# LED_Cube.net
KiCad netlist of a schematic drawn in EAGLE
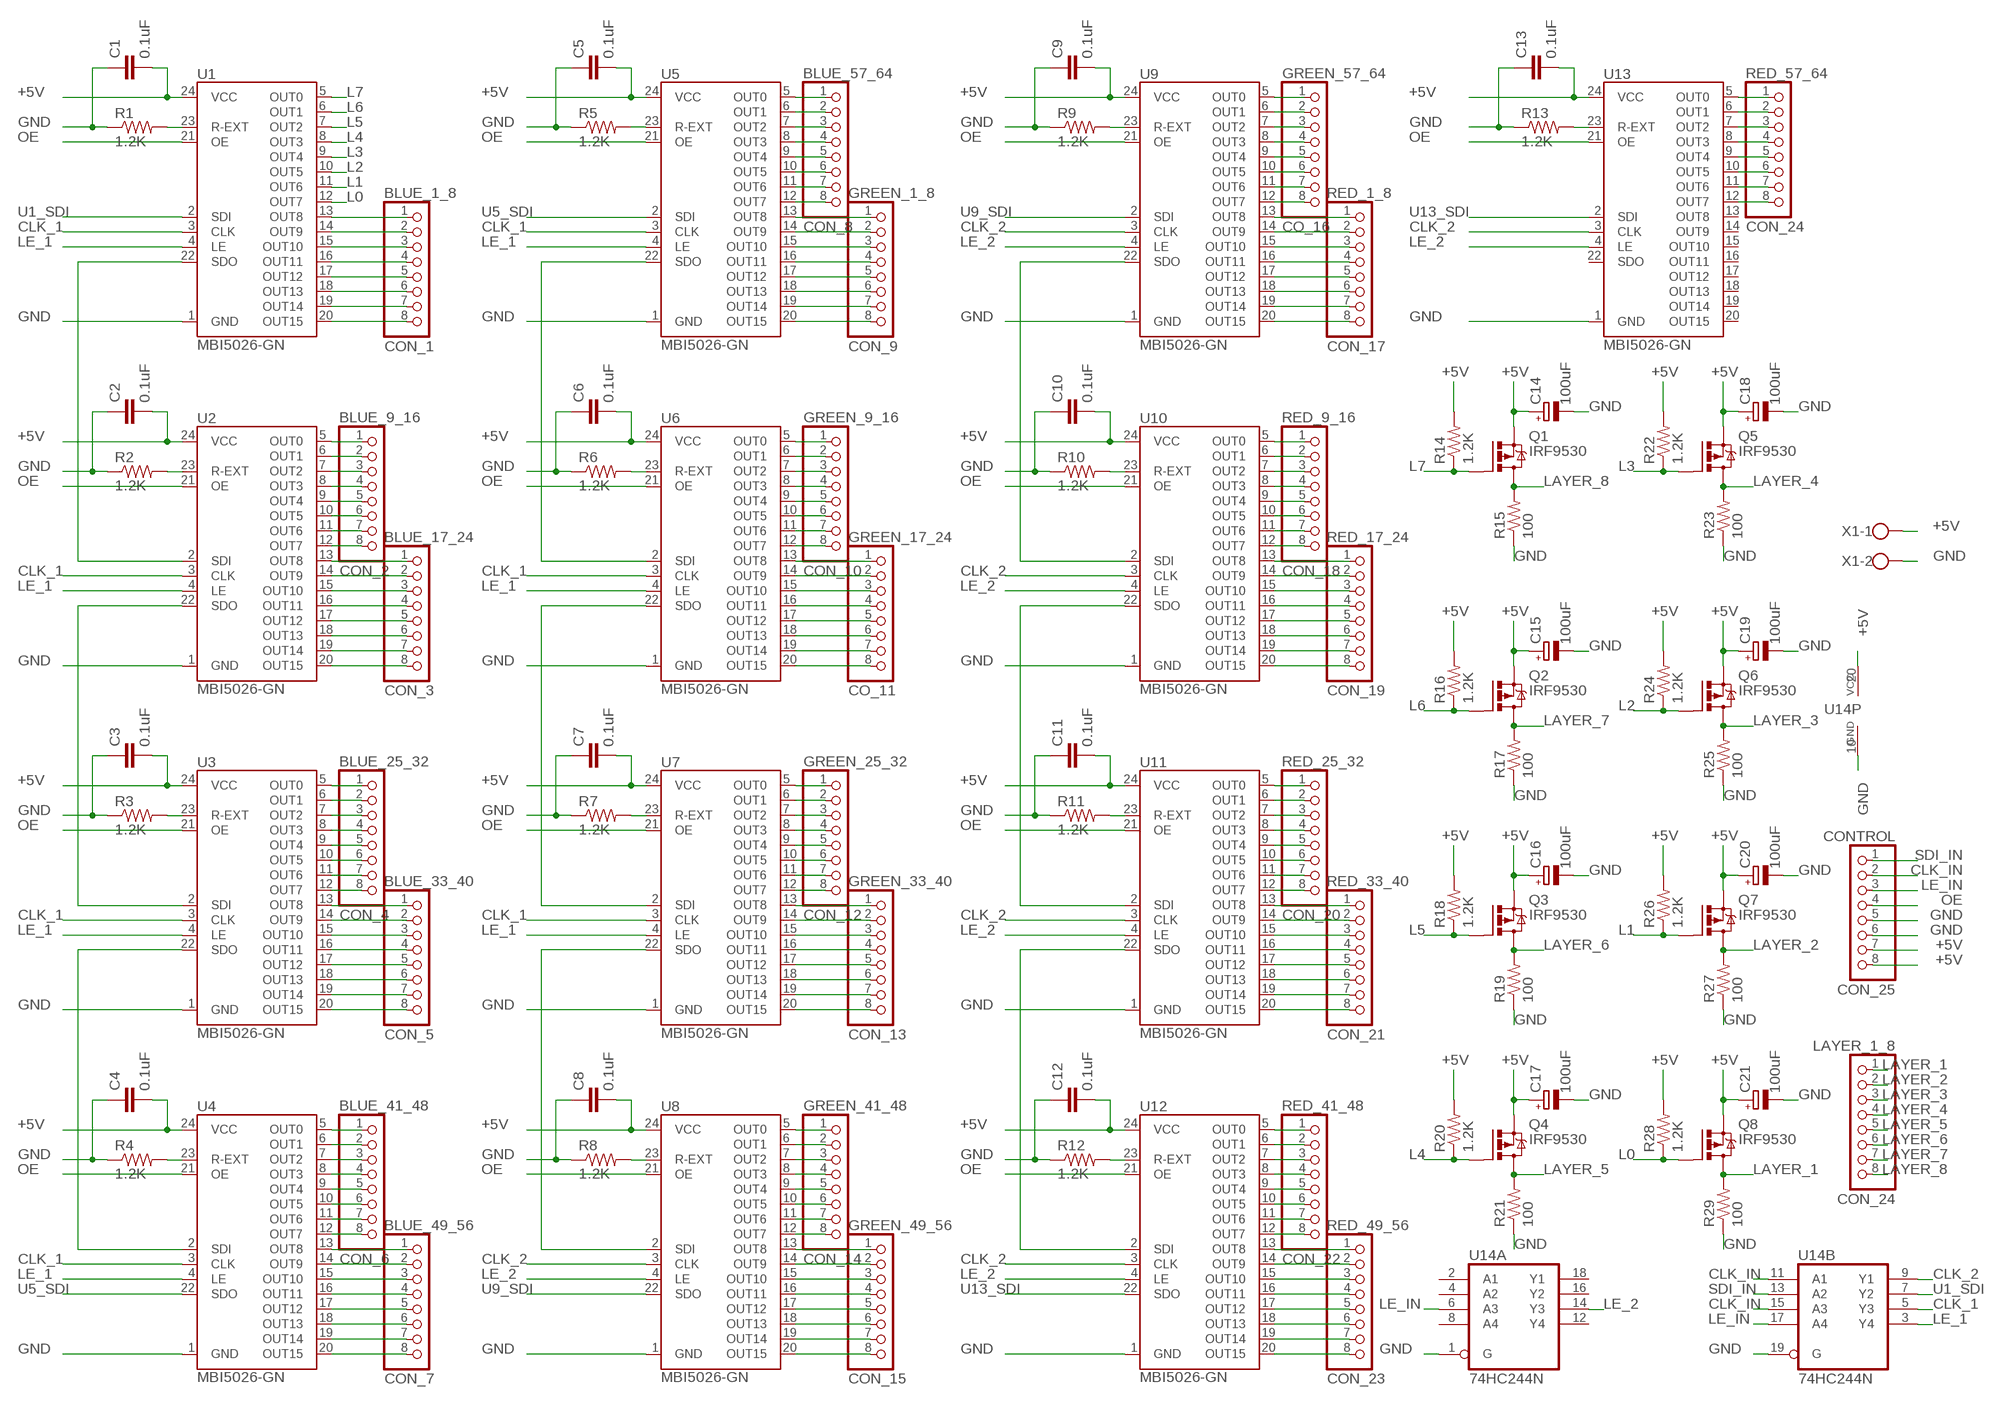
[diagram p0: schematic, sheet 1]

(export (version "E")
  (design (tool "Eeschema 10.0.6"))
  (components
    (comp (ref "BLUE_1_8")
      (value "CON_1")
      (footprint "eagle-import:1X08-BIG")
      (libsource (lib "eagle-import") (part "PINHD-1X8BIG"))
    )
    (comp (ref "BLUE_9_16")
      (value "CON_2")
      (footprint "eagle-import:1X08-BIG")
      (libsource (lib "eagle-import") (part "PINHD-1X8BIG"))
    )
    (comp (ref "BLUE_17_24")
      (value "CON_3")
      (footprint "eagle-import:1X08-BIG")
      (libsource (lib "eagle-import") (part "PINHD-1X8BIG"))
    )
    (comp (ref "BLUE_25_32")
      (value "CON_4")
      (footprint "eagle-import:1X08-BIG")
      (libsource (lib "eagle-import") (part "PINHD-1X8BIG"))
    )
    (comp (ref "BLUE_33_40")
      (value "CON_5")
      (footprint "eagle-import:1X08-BIG")
      (libsource (lib "eagle-import") (part "PINHD-1X8BIG"))
    )
    (comp (ref "BLUE_41_48")
      (value "CON_6")
      (footprint "eagle-import:1X08-BIG")
      (libsource (lib "eagle-import") (part "PINHD-1X8BIG"))
    )
    (comp (ref "BLUE_49_56")
      (value "CON_7")
      (footprint "eagle-import:1X08-BIG")
      (libsource (lib "eagle-import") (part "PINHD-1X8BIG"))
    )
    (comp (ref "BLUE_57_64")
      (value "CON_8")
      (footprint "eagle-import:1X08-BIG")
      (libsource (lib "eagle-import") (part "PINHD-1X8BIG"))
    )
    (comp (ref "C1")
      (value "0.1uF")
      (footprint "eagle-import:C2.5-3")
      (libsource (lib "eagle-import") (part "C2,5-3"))
    )
    (comp (ref "C2")
      (value "0.1uF")
      (footprint "eagle-import:C2.5-3")
      (libsource (lib "eagle-import") (part "C2,5-3"))
    )
    (comp (ref "C3")
      (value "0.1uF")
      (footprint "eagle-import:C2.5-3")
      (libsource (lib "eagle-import") (part "C2,5-3"))
    )
    (comp (ref "C4")
      (value "0.1uF")
      (footprint "eagle-import:C2.5-3")
      (libsource (lib "eagle-import") (part "C2,5-3"))
    )
    (comp (ref "C5")
      (value "0.1uF")
      (footprint "eagle-import:C2.5-3")
      (libsource (lib "eagle-import") (part "C2,5-3"))
    )
    (comp (ref "C6")
      (value "0.1uF")
      (footprint "eagle-import:C2.5-3")
      (libsource (lib "eagle-import") (part "C2,5-3"))
    )
    (comp (ref "C7")
      (value "0.1uF")
      (footprint "eagle-import:C2.5-3")
      (libsource (lib "eagle-import") (part "C2,5-3"))
    )
    (comp (ref "C8")
      (value "0.1uF")
      (footprint "eagle-import:C2.5-3")
      (libsource (lib "eagle-import") (part "C2,5-3"))
    )
    (comp (ref "C9")
      (value "0.1uF")
      (footprint "eagle-import:C2.5-3")
      (libsource (lib "eagle-import") (part "C2,5-3"))
    )
    (comp (ref "C10")
      (value "0.1uF")
      (footprint "eagle-import:C2.5-3")
      (libsource (lib "eagle-import") (part "C2,5-3"))
    )
    (comp (ref "C11")
      (value "0.1uF")
      (footprint "eagle-import:C2.5-3")
      (libsource (lib "eagle-import") (part "C2,5-3"))
    )
    (comp (ref "C12")
      (value "0.1uF")
      (footprint "eagle-import:C2.5-3")
      (libsource (lib "eagle-import") (part "C2,5-3"))
    )
    (comp (ref "C13")
      (value "0.1uF")
      (footprint "eagle-import:C2.5-3")
      (libsource (lib "eagle-import") (part "C2,5-3"))
    )
    (comp (ref "C14")
      (value "100uF")
      (footprint "eagle-import:E5-6")
      (libsource (lib "eagle-import") (part "CPOL-EUE5-6"))
    )
    (comp (ref "C15")
      (value "100uF")
      (footprint "eagle-import:E5-6")
      (libsource (lib "eagle-import") (part "CPOL-EUE5-6"))
    )
    (comp (ref "C16")
      (value "100uF")
      (footprint "eagle-import:E5-6")
      (libsource (lib "eagle-import") (part "CPOL-EUE5-6"))
    )
    (comp (ref "C17")
      (value "100uF")
      (footprint "eagle-import:E5-6")
      (libsource (lib "eagle-import") (part "CPOL-EUE5-6"))
    )
    (comp (ref "C18")
      (value "100uF")
      (footprint "eagle-import:E5-6")
      (libsource (lib "eagle-import") (part "CPOL-EUE5-6"))
    )
    (comp (ref "C19")
      (value "100uF")
      (footprint "eagle-import:E5-6")
      (libsource (lib "eagle-import") (part "CPOL-EUE5-6"))
    )
    (comp (ref "C20")
      (value "100uF")
      (footprint "eagle-import:E5-6")
      (libsource (lib "eagle-import") (part "CPOL-EUE5-6"))
    )
    (comp (ref "C21")
      (value "100uF")
      (footprint "eagle-import:E5-6")
      (libsource (lib "eagle-import") (part "CPOL-EUE5-6"))
    )
    (comp (ref "CONTROL")
      (value "CON_25")
      (footprint "eagle-import:1X08-BIG")
      (libsource (lib "eagle-import") (part "PINHD-1X8BIG"))
    )
    (comp (ref "GREEN_1_8")
      (value "CON_9")
      (footprint "eagle-import:1X08-BIG")
      (libsource (lib "eagle-import") (part "PINHD-1X8BIG"))
    )
    (comp (ref "GREEN_9_16")
      (value "CON_10")
      (footprint "eagle-import:1X08-BIG")
      (libsource (lib "eagle-import") (part "PINHD-1X8BIG"))
    )
    (comp (ref "GREEN_17_24")
      (value "CO_11")
      (footprint "eagle-import:1X08-BIG")
      (libsource (lib "eagle-import") (part "PINHD-1X8BIG"))
    )
    (comp (ref "GREEN_25_32")
      (value "CON_12")
      (footprint "eagle-import:1X08-BIG")
      (libsource (lib "eagle-import") (part "PINHD-1X8BIG"))
    )
    (comp (ref "GREEN_33_40")
      (value "CON_13")
      (footprint "eagle-import:1X08-BIG")
      (libsource (lib "eagle-import") (part "PINHD-1X8BIG"))
    )
    (comp (ref "GREEN_41_48")
      (value "CON_14")
      (footprint "eagle-import:1X08-BIG")
      (libsource (lib "eagle-import") (part "PINHD-1X8BIG"))
    )
    (comp (ref "GREEN_49_56")
      (value "CON_15")
      (footprint "eagle-import:1X08-BIG")
      (libsource (lib "eagle-import") (part "PINHD-1X8BIG"))
    )
    (comp (ref "GREEN_57_64")
      (value "CO_16")
      (footprint "eagle-import:1X08-BIG")
      (libsource (lib "eagle-import") (part "PINHD-1X8BIG"))
    )
    (comp (ref "LAYER_1_8")
      (value "CON_24")
      (footprint "eagle-import:1X08-BIG")
      (libsource (lib "eagle-import") (part "PINHD-1X8BIG"))
    )
    (comp (ref "Q1")
      (value "IRF9530")
      (footprint "eagle-import:TO220BV")
      (libsource (lib "eagle-import") (part "IRF9530"))
    )
    (comp (ref "Q2")
      (value "IRF9530")
      (footprint "eagle-import:TO220BV")
      (libsource (lib "eagle-import") (part "IRF9530"))
    )
    (comp (ref "Q3")
      (value "IRF9530")
      (footprint "eagle-import:TO220BV")
      (libsource (lib "eagle-import") (part "IRF9530"))
    )
    (comp (ref "Q4")
      (value "IRF9530")
      (footprint "eagle-import:TO220BV")
      (libsource (lib "eagle-import") (part "IRF9530"))
    )
    (comp (ref "Q5")
      (value "IRF9530")
      (footprint "eagle-import:TO220BV")
      (libsource (lib "eagle-import") (part "IRF9530"))
    )
    (comp (ref "Q6")
      (value "IRF9530")
      (footprint "eagle-import:TO220BV")
      (libsource (lib "eagle-import") (part "IRF9530"))
    )
    (comp (ref "Q7")
      (value "IRF9530")
      (footprint "eagle-import:TO220BV")
      (libsource (lib "eagle-import") (part "IRF9530"))
    )
    (comp (ref "Q8")
      (value "IRF9530")
      (footprint "eagle-import:TO220BV")
      (libsource (lib "eagle-import") (part "IRF9530"))
    )
    (comp (ref "R1")
      (value "1.2K")
      (footprint "eagle-import:0207_15")
      (libsource (lib "eagle-import") (part "R-US_0207/15"))
    )
    (comp (ref "R2")
      (value "1.2K")
      (footprint "eagle-import:0207_15")
      (libsource (lib "eagle-import") (part "R-US_0207/15"))
    )
    (comp (ref "R3")
      (value "1.2K")
      (footprint "eagle-import:0207_15")
      (libsource (lib "eagle-import") (part "R-US_0207/15"))
    )
    (comp (ref "R4")
      (value "1.2K")
      (footprint "eagle-import:0207_15")
      (libsource (lib "eagle-import") (part "R-US_0207/15"))
    )
    (comp (ref "R5")
      (value "1.2K")
      (footprint "eagle-import:0207_15")
      (libsource (lib "eagle-import") (part "R-US_0207/15"))
    )
    (comp (ref "R6")
      (value "1.2K")
      (footprint "eagle-import:0207_15")
      (libsource (lib "eagle-import") (part "R-US_0207/15"))
    )
    (comp (ref "R7")
      (value "1.2K")
      (footprint "eagle-import:0207_15")
      (libsource (lib "eagle-import") (part "R-US_0207/15"))
    )
    (comp (ref "R8")
      (value "1.2K")
      (footprint "eagle-import:0207_15")
      (libsource (lib "eagle-import") (part "R-US_0207/15"))
    )
    (comp (ref "R9")
      (value "1.2K")
      (footprint "eagle-import:0207_15")
      (libsource (lib "eagle-import") (part "R-US_0207/15"))
    )
    (comp (ref "R10")
      (value "1.2K")
      (footprint "eagle-import:0207_15")
      (libsource (lib "eagle-import") (part "R-US_0207/15"))
    )
    (comp (ref "R11")
      (value "1.2K")
      (footprint "eagle-import:0207_15")
      (libsource (lib "eagle-import") (part "R-US_0207/15"))
    )
    (comp (ref "R12")
      (value "1.2K")
      (footprint "eagle-import:0207_15")
      (libsource (lib "eagle-import") (part "R-US_0207/15"))
    )
    (comp (ref "R13")
      (value "1.2K")
      (footprint "eagle-import:0207_15")
      (libsource (lib "eagle-import") (part "R-US_0207/15"))
    )
    (comp (ref "R14")
      (value "1.2K")
      (footprint "eagle-import:0207_15")
      (libsource (lib "eagle-import") (part "R-US_0207/15"))
    )
    (comp (ref "R15")
      (value "100")
      (footprint "eagle-import:0207_15")
      (libsource (lib "eagle-import") (part "R-US_0207/15"))
    )
    (comp (ref "R16")
      (value "1.2K")
      (footprint "eagle-import:0207_15")
      (libsource (lib "eagle-import") (part "R-US_0207/15"))
    )
    (comp (ref "R17")
      (value "100")
      (footprint "eagle-import:0207_15")
      (libsource (lib "eagle-import") (part "R-US_0207/15"))
    )
    (comp (ref "R18")
      (value "1.2K")
      (footprint "eagle-import:0207_15")
      (libsource (lib "eagle-import") (part "R-US_0207/15"))
    )
    (comp (ref "R19")
      (value "100")
      (footprint "eagle-import:0207_15")
      (libsource (lib "eagle-import") (part "R-US_0207/15"))
    )
    (comp (ref "R20")
      (value "1.2K")
      (footprint "eagle-import:0207_15")
      (libsource (lib "eagle-import") (part "R-US_0207/15"))
    )
    (comp (ref "R21")
      (value "100")
      (footprint "eagle-import:0207_15")
      (libsource (lib "eagle-import") (part "R-US_0207/15"))
    )
    (comp (ref "R22")
      (value "1.2K")
      (footprint "eagle-import:0207_15")
      (libsource (lib "eagle-import") (part "R-US_0207/15"))
    )
    (comp (ref "R23")
      (value "100")
      (footprint "eagle-import:0207_15")
      (libsource (lib "eagle-import") (part "R-US_0207/15"))
    )
    (comp (ref "R24")
      (value "1.2K")
      (footprint "eagle-import:0207_15")
      (libsource (lib "eagle-import") (part "R-US_0207/15"))
    )
    (comp (ref "R25")
      (value "100")
      (footprint "eagle-import:0207_15")
      (libsource (lib "eagle-import") (part "R-US_0207/15"))
    )
    (comp (ref "R26")
      (value "1.2K")
      (footprint "eagle-import:0207_15")
      (libsource (lib "eagle-import") (part "R-US_0207/15"))
    )
    (comp (ref "R27")
      (value "100")
      (footprint "eagle-import:0207_15")
      (libsource (lib "eagle-import") (part "R-US_0207/15"))
    )
    (comp (ref "R28")
      (value "1.2K")
      (footprint "eagle-import:0207_15")
      (libsource (lib "eagle-import") (part "R-US_0207/15"))
    )
    (comp (ref "R29")
      (value "100")
      (footprint "eagle-import:0207_15")
      (libsource (lib "eagle-import") (part "R-US_0207/15"))
    )
    (comp (ref "RED_1_8")
      (value "CON_17")
      (footprint "eagle-import:1X08-BIG")
      (libsource (lib "eagle-import") (part "PINHD-1X8BIG"))
    )
    (comp (ref "RED_9_16")
      (value "CON_18")
      (footprint "eagle-import:1X08-BIG")
      (libsource (lib "eagle-import") (part "PINHD-1X8BIG"))
    )
    (comp (ref "RED_17_24")
      (value "CON_19")
      (footprint "eagle-import:1X08-BIG")
      (libsource (lib "eagle-import") (part "PINHD-1X8BIG"))
    )
    (comp (ref "RED_25_32")
      (value "CON_20")
      (footprint "eagle-import:1X08-BIG")
      (libsource (lib "eagle-import") (part "PINHD-1X8BIG"))
    )
    (comp (ref "RED_33_40")
      (value "CON_21")
      (footprint "eagle-import:1X08-BIG")
      (libsource (lib "eagle-import") (part "PINHD-1X8BIG"))
    )
    (comp (ref "RED_41_48")
      (value "CON_22")
      (footprint "eagle-import:1X08-BIG")
      (libsource (lib "eagle-import") (part "PINHD-1X8BIG"))
    )
    (comp (ref "RED_49_56")
      (value "CON_23")
      (footprint "eagle-import:1X08-BIG")
      (libsource (lib "eagle-import") (part "PINHD-1X8BIG"))
    )
    (comp (ref "RED_57_64")
      (value "CON_24")
      (footprint "eagle-import:1X08-BIG")
      (libsource (lib "eagle-import") (part "PINHD-1X8BIG"))
    )
    (comp (ref "U1")
      (value "MBI5026-GN")
      (footprint "eagle-import:DIL24-3")
      (libsource (lib "eagle-import") (part "MBI5026-GN"))
    )
    (comp (ref "U2")
      (value "MBI5026-GN")
      (footprint "eagle-import:DIL24-3")
      (libsource (lib "eagle-import") (part "MBI5026-GN"))
    )
    (comp (ref "U3")
      (value "MBI5026-GN")
      (footprint "eagle-import:DIL24-3")
      (libsource (lib "eagle-import") (part "MBI5026-GN"))
    )
    (comp (ref "U4")
      (value "MBI5026-GN")
      (footprint "eagle-import:DIL24-3")
      (libsource (lib "eagle-import") (part "MBI5026-GN"))
    )
    (comp (ref "U5")
      (value "MBI5026-GN")
      (footprint "eagle-import:DIL24-3")
      (libsource (lib "eagle-import") (part "MBI5026-GN"))
    )
    (comp (ref "U6")
      (value "MBI5026-GN")
      (footprint "eagle-import:DIL24-3")
      (libsource (lib "eagle-import") (part "MBI5026-GN"))
    )
    (comp (ref "U7")
      (value "MBI5026-GN")
      (footprint "eagle-import:DIL24-3")
      (libsource (lib "eagle-import") (part "MBI5026-GN"))
    )
    (comp (ref "U8")
      (value "MBI5026-GN")
      (footprint "eagle-import:DIL24-3")
      (libsource (lib "eagle-import") (part "MBI5026-GN"))
    )
    (comp (ref "U9")
      (value "MBI5026-GN")
      (footprint "eagle-import:DIL24-3")
      (libsource (lib "eagle-import") (part "MBI5026-GN"))
    )
    (comp (ref "U10")
      (value "MBI5026-GN")
      (footprint "eagle-import:DIL24-3")
      (libsource (lib "eagle-import") (part "MBI5026-GN"))
    )
    (comp (ref "U11")
      (value "MBI5026-GN")
      (footprint "eagle-import:DIL24-3")
      (libsource (lib "eagle-import") (part "MBI5026-GN"))
    )
    (comp (ref "U12")
      (value "MBI5026-GN")
      (footprint "eagle-import:DIL24-3")
      (libsource (lib "eagle-import") (part "MBI5026-GN"))
    )
    (comp (ref "U13")
      (value "MBI5026-GN")
      (footprint "eagle-import:DIL24-3")
      (libsource (lib "eagle-import") (part "MBI5026-GN"))
    )
    (comp (ref "U14")
      (value "74HC244N")
      (footprint "eagle-import:DIL20")
      (libsource (lib "eagle-import") (part "74244NHC"))
    )
    (comp (ref "X1")
      (value "W237-102")
      (footprint "eagle-import:W237-102")
      (fields (field (name "MPN") "237-102"))
      (libsource (lib "eagle-import") (part "W237-102"))
    )
  )
  (nets
    (net (code "1") (name "/+5V") (class "Default")
      (node (ref "C1") (pin "2") (pinfunction "2_2") (pintype "passive"))
      (node (ref "C10") (pin "2") (pinfunction "2_2") (pintype "passive"))
      (node (ref "C11") (pin "2") (pinfunction "2_2") (pintype "passive"))
      (node (ref "C12") (pin "2") (pinfunction "2_2") (pintype "passive"))
      (node (ref "C13") (pin "2") (pinfunction "2_2") (pintype "passive"))
      (node (ref "C14") (pin "+") (pinfunction "+_+") (pintype "passive"))
      (node (ref "C15") (pin "+") (pinfunction "+_+") (pintype "passive"))
      (node (ref "C16") (pin "+") (pinfunction "+_+") (pintype "passive"))
      (node (ref "C17") (pin "+") (pinfunction "+_+") (pintype "passive"))
      (node (ref "C18") (pin "+") (pinfunction "+_+") (pintype "passive"))
      (node (ref "C19") (pin "+") (pinfunction "+_+") (pintype "passive"))
      (node (ref "C2") (pin "2") (pinfunction "2_2") (pintype "passive"))
      (node (ref "C20") (pin "+") (pinfunction "+_+") (pintype "passive"))
      (node (ref "C21") (pin "+") (pinfunction "+_+") (pintype "passive"))
      (node (ref "C3") (pin "2") (pinfunction "2_2") (pintype "passive"))
      (node (ref "C4") (pin "2") (pinfunction "2_2") (pintype "passive"))
      (node (ref "C5") (pin "2") (pinfunction "2_2") (pintype "passive"))
      (node (ref "C6") (pin "2") (pinfunction "2_2") (pintype "passive"))
      (node (ref "C7") (pin "2") (pinfunction "2_2") (pintype "passive"))
      (node (ref "C8") (pin "2") (pinfunction "2_2") (pintype "passive"))
      (node (ref "C9") (pin "2") (pinfunction "2_2") (pintype "passive"))
      (node (ref "CONTROL") (pin "7") (pinfunction "7_7") (pintype "passive"))
      (node (ref "CONTROL") (pin "8") (pinfunction "8_8") (pintype "passive"))
      (node (ref "Q1") (pin "S") (pinfunction "S_S") (pintype "passive"))
      (node (ref "Q2") (pin "S") (pinfunction "S_S") (pintype "passive"))
      (node (ref "Q3") (pin "S") (pinfunction "S_S") (pintype "passive"))
      (node (ref "Q4") (pin "S") (pinfunction "S_S") (pintype "passive"))
      (node (ref "Q5") (pin "S") (pinfunction "S_S") (pintype "passive"))
      (node (ref "Q6") (pin "S") (pinfunction "S_S") (pintype "passive"))
      (node (ref "Q7") (pin "S") (pinfunction "S_S") (pintype "passive"))
      (node (ref "Q8") (pin "S") (pinfunction "S_S") (pintype "passive"))
      (node (ref "R14") (pin "2") (pinfunction "2_2") (pintype "passive"))
      (node (ref "R16") (pin "2") (pinfunction "2_2") (pintype "passive"))
      (node (ref "R18") (pin "2") (pinfunction "2_2") (pintype "passive"))
      (node (ref "R20") (pin "2") (pinfunction "2_2") (pintype "passive"))
      (node (ref "R22") (pin "2") (pinfunction "2_2") (pintype "passive"))
      (node (ref "R24") (pin "2") (pinfunction "2_2") (pintype "passive"))
      (node (ref "R26") (pin "2") (pinfunction "2_2") (pintype "passive"))
      (node (ref "R28") (pin "2") (pinfunction "2_2") (pintype "passive"))
      (node (ref "U1") (pin "24") (pinfunction "VCC_24") (pintype "bidirectional"))
      (node (ref "U10") (pin "24") (pinfunction "VCC_24") (pintype "bidirectional"))
      (node (ref "U11") (pin "24") (pinfunction "VCC_24") (pintype "bidirectional"))
      (node (ref "U12") (pin "24") (pinfunction "VCC_24") (pintype "bidirectional"))
      (node (ref "U13") (pin "24") (pinfunction "VCC_24") (pintype "bidirectional"))
      (node (ref "U14") (pin "20") (pinfunction "VCC_20") (pintype "power_in"))
      (node (ref "U2") (pin "24") (pinfunction "VCC_24") (pintype "bidirectional"))
      (node (ref "U3") (pin "24") (pinfunction "VCC_24") (pintype "bidirectional"))
      (node (ref "U4") (pin "24") (pinfunction "VCC_24") (pintype "bidirectional"))
      (node (ref "U5") (pin "24") (pinfunction "VCC_24") (pintype "bidirectional"))
      (node (ref "U6") (pin "24") (pinfunction "VCC_24") (pintype "bidirectional"))
      (node (ref "U7") (pin "24") (pinfunction "VCC_24") (pintype "bidirectional"))
      (node (ref "U8") (pin "24") (pinfunction "VCC_24") (pintype "bidirectional"))
      (node (ref "U9") (pin "24") (pinfunction "VCC_24") (pintype "bidirectional"))
      (node (ref "X1") (pin "1") (pinfunction "KL_1") (pintype "passive"))
    )
    (net (code "2") (name "/CLK_1") (class "Default")
      (node (ref "U1") (pin "3") (pinfunction "CLK_3") (pintype "bidirectional"))
      (node (ref "U14") (pin "5") (pinfunction "Y3_5") (pintype "tri_state"))
      (node (ref "U2") (pin "3") (pinfunction "CLK_3") (pintype "bidirectional"))
      (node (ref "U3") (pin "3") (pinfunction "CLK_3") (pintype "bidirectional"))
      (node (ref "U4") (pin "3") (pinfunction "CLK_3") (pintype "bidirectional"))
      (node (ref "U5") (pin "3") (pinfunction "CLK_3") (pintype "bidirectional"))
      (node (ref "U6") (pin "3") (pinfunction "CLK_3") (pintype "bidirectional"))
      (node (ref "U7") (pin "3") (pinfunction "CLK_3") (pintype "bidirectional"))
    )
    (net (code "3") (name "/CLK_2") (class "Default")
      (node (ref "U10") (pin "3") (pinfunction "CLK_3") (pintype "bidirectional"))
      (node (ref "U11") (pin "3") (pinfunction "CLK_3") (pintype "bidirectional"))
      (node (ref "U12") (pin "3") (pinfunction "CLK_3") (pintype "bidirectional"))
      (node (ref "U13") (pin "3") (pinfunction "CLK_3") (pintype "bidirectional"))
      (node (ref "U14") (pin "9") (pinfunction "Y1_9") (pintype "tri_state"))
      (node (ref "U8") (pin "3") (pinfunction "CLK_3") (pintype "bidirectional"))
      (node (ref "U9") (pin "3") (pinfunction "CLK_3") (pintype "bidirectional"))
    )
    (net (code "4") (name "/CLK_IN") (class "Default")
      (node (ref "CONTROL") (pin "2") (pinfunction "2_2") (pintype "passive"))
      (node (ref "U14") (pin "11") (pinfunction "A1_11") (pintype "input"))
      (node (ref "U14") (pin "15") (pinfunction "A3_15") (pintype "input"))
    )
    (net (code "5") (name "/GND") (class "Default")
      (node (ref "C1") (pin "1") (pinfunction "1_1") (pintype "passive"))
      (node (ref "C10") (pin "1") (pinfunction "1_1") (pintype "passive"))
      (node (ref "C11") (pin "1") (pinfunction "1_1") (pintype "passive"))
      (node (ref "C12") (pin "1") (pinfunction "1_1") (pintype "passive"))
      (node (ref "C13") (pin "1") (pinfunction "1_1") (pintype "passive"))
      (node (ref "C14") (pin "-") (pinfunction "-_-") (pintype "passive"))
      (node (ref "C15") (pin "-") (pinfunction "-_-") (pintype "passive"))
      (node (ref "C16") (pin "-") (pinfunction "-_-") (pintype "passive"))
      (node (ref "C17") (pin "-") (pinfunction "-_-") (pintype "passive"))
      (node (ref "C18") (pin "-") (pinfunction "-_-") (pintype "passive"))
      (node (ref "C19") (pin "-") (pinfunction "-_-") (pintype "passive"))
      (node (ref "C2") (pin "1") (pinfunction "1_1") (pintype "passive"))
      (node (ref "C20") (pin "-") (pinfunction "-_-") (pintype "passive"))
      (node (ref "C21") (pin "-") (pinfunction "-_-") (pintype "passive"))
      (node (ref "C3") (pin "1") (pinfunction "1_1") (pintype "passive"))
      (node (ref "C4") (pin "1") (pinfunction "1_1") (pintype "passive"))
      (node (ref "C5") (pin "1") (pinfunction "1_1") (pintype "passive"))
      (node (ref "C6") (pin "1") (pinfunction "1_1") (pintype "passive"))
      (node (ref "C7") (pin "1") (pinfunction "1_1") (pintype "passive"))
      (node (ref "C8") (pin "1") (pinfunction "1_1") (pintype "passive"))
      (node (ref "C9") (pin "1") (pinfunction "1_1") (pintype "passive"))
      (node (ref "CONTROL") (pin "5") (pinfunction "5_5") (pintype "passive"))
      (node (ref "CONTROL") (pin "6") (pinfunction "6_6") (pintype "passive"))
      (node (ref "R1") (pin "1") (pinfunction "1_1") (pintype "passive"))
      (node (ref "R10") (pin "1") (pinfunction "1_1") (pintype "passive"))
      (node (ref "R11") (pin "1") (pinfunction "1_1") (pintype "passive"))
      (node (ref "R12") (pin "1") (pinfunction "1_1") (pintype "passive"))
      (node (ref "R13") (pin "1") (pinfunction "1_1") (pintype "passive"))
      (node (ref "R15") (pin "1") (pinfunction "1_1") (pintype "passive"))
      (node (ref "R17") (pin "1") (pinfunction "1_1") (pintype "passive"))
      (node (ref "R19") (pin "1") (pinfunction "1_1") (pintype "passive"))
      (node (ref "R2") (pin "1") (pinfunction "1_1") (pintype "passive"))
      (node (ref "R21") (pin "1") (pinfunction "1_1") (pintype "passive"))
      (node (ref "R23") (pin "1") (pinfunction "1_1") (pintype "passive"))
      (node (ref "R25") (pin "1") (pinfunction "1_1") (pintype "passive"))
      (node (ref "R27") (pin "1") (pinfunction "1_1") (pintype "passive"))
      (node (ref "R29") (pin "1") (pinfunction "1_1") (pintype "passive"))
      (node (ref "R3") (pin "1") (pinfunction "1_1") (pintype "passive"))
      (node (ref "R4") (pin "1") (pinfunction "1_1") (pintype "passive"))
      (node (ref "R5") (pin "1") (pinfunction "1_1") (pintype "passive"))
      (node (ref "R6") (pin "1") (pinfunction "1_1") (pintype "passive"))
      (node (ref "R7") (pin "1") (pinfunction "1_1") (pintype "passive"))
      (node (ref "R8") (pin "1") (pinfunction "1_1") (pintype "passive"))
      (node (ref "R9") (pin "1") (pinfunction "1_1") (pintype "passive"))
      (node (ref "U1") (pin "1") (pinfunction "GND_1") (pintype "bidirectional"))
      (node (ref "U10") (pin "1") (pinfunction "GND_1") (pintype "bidirectional"))
      (node (ref "U11") (pin "1") (pinfunction "GND_1") (pintype "bidirectional"))
      (node (ref "U12") (pin "1") (pinfunction "GND_1") (pintype "bidirectional"))
      (node (ref "U13") (pin "1") (pinfunction "GND_1") (pintype "bidirectional"))
      (node (ref "U14") (pin "1") (pinfunction "G_1") (pintype "input"))
      (node (ref "U14") (pin "10") (pinfunction "GND_10") (pintype "power_in"))
      (node (ref "U14") (pin "19") (pinfunction "G_19") (pintype "input"))
      (node (ref "U2") (pin "1") (pinfunction "GND_1") (pintype "bidirectional"))
      (node (ref "U3") (pin "1") (pinfunction "GND_1") (pintype "bidirectional"))
      (node (ref "U4") (pin "1") (pinfunction "GND_1") (pintype "bidirectional"))
      (node (ref "U5") (pin "1") (pinfunction "GND_1") (pintype "bidirectional"))
      (node (ref "U6") (pin "1") (pinfunction "GND_1") (pintype "bidirectional"))
      (node (ref "U7") (pin "1") (pinfunction "GND_1") (pintype "bidirectional"))
      (node (ref "U8") (pin "1") (pinfunction "GND_1") (pintype "bidirectional"))
      (node (ref "U9") (pin "1") (pinfunction "GND_1") (pintype "bidirectional"))
      (node (ref "X1") (pin "2") (pinfunction "KL_2") (pintype "passive"))
    )
    (net (code "6") (name "/L0") (class "Default")
      (node (ref "Q8") (pin "G") (pinfunction "G_G") (pintype "passive"))
      (node (ref "R28") (pin "1") (pinfunction "1_1") (pintype "passive"))
      (node (ref "U1") (pin "12") (pinfunction "OUT7_12") (pintype "bidirectional"))
    )
    (net (code "7") (name "/L1") (class "Default")
      (node (ref "Q7") (pin "G") (pinfunction "G_G") (pintype "passive"))
      (node (ref "R26") (pin "1") (pinfunction "1_1") (pintype "passive"))
      (node (ref "U1") (pin "11") (pinfunction "OUT6_11") (pintype "bidirectional"))
    )
    (net (code "8") (name "/L2") (class "Default")
      (node (ref "Q6") (pin "G") (pinfunction "G_G") (pintype "passive"))
      (node (ref "R24") (pin "1") (pinfunction "1_1") (pintype "passive"))
      (node (ref "U1") (pin "10") (pinfunction "OUT5_10") (pintype "bidirectional"))
    )
    (net (code "9") (name "/L3") (class "Default")
      (node (ref "Q5") (pin "G") (pinfunction "G_G") (pintype "passive"))
      (node (ref "R22") (pin "1") (pinfunction "1_1") (pintype "passive"))
      (node (ref "U1") (pin "9") (pinfunction "OUT4_9") (pintype "bidirectional"))
    )
    (net (code "10") (name "/L4") (class "Default")
      (node (ref "Q4") (pin "G") (pinfunction "G_G") (pintype "passive"))
      (node (ref "R20") (pin "1") (pinfunction "1_1") (pintype "passive"))
      (node (ref "U1") (pin "8") (pinfunction "OUT3_8") (pintype "bidirectional"))
    )
    (net (code "11") (name "/L5") (class "Default")
      (node (ref "Q3") (pin "G") (pinfunction "G_G") (pintype "passive"))
      (node (ref "R18") (pin "1") (pinfunction "1_1") (pintype "passive"))
      (node (ref "U1") (pin "7") (pinfunction "OUT2_7") (pintype "bidirectional"))
    )
    (net (code "12") (name "/L6") (class "Default")
      (node (ref "Q2") (pin "G") (pinfunction "G_G") (pintype "passive"))
      (node (ref "R16") (pin "1") (pinfunction "1_1") (pintype "passive"))
      (node (ref "U1") (pin "6") (pinfunction "OUT1_6") (pintype "bidirectional"))
    )
    (net (code "13") (name "/L7") (class "Default")
      (node (ref "Q1") (pin "G") (pinfunction "G_G") (pintype "passive"))
      (node (ref "R14") (pin "1") (pinfunction "1_1") (pintype "passive"))
      (node (ref "U1") (pin "5") (pinfunction "OUT0_5") (pintype "bidirectional"))
    )
    (net (code "14") (name "/LAYER_1") (class "Default")
      (node (ref "LAYER_1_8") (pin "1") (pinfunction "1_1") (pintype "passive"))
      (node (ref "Q8") (pin "D") (pinfunction "D_D") (pintype "passive"))
      (node (ref "R29") (pin "2") (pinfunction "2_2") (pintype "passive"))
    )
    (net (code "15") (name "/LAYER_2") (class "Default")
      (node (ref "LAYER_1_8") (pin "2") (pinfunction "2_2") (pintype "passive"))
      (node (ref "Q7") (pin "D") (pinfunction "D_D") (pintype "passive"))
      (node (ref "R27") (pin "2") (pinfunction "2_2") (pintype "passive"))
    )
    (net (code "16") (name "/LAYER_3") (class "Default")
      (node (ref "LAYER_1_8") (pin "3") (pinfunction "3_3") (pintype "passive"))
      (node (ref "Q6") (pin "D") (pinfunction "D_D") (pintype "passive"))
      (node (ref "R25") (pin "2") (pinfunction "2_2") (pintype "passive"))
    )
    (net (code "17") (name "/LAYER_4") (class "Default")
      (node (ref "LAYER_1_8") (pin "4") (pinfunction "4_4") (pintype "passive"))
      (node (ref "Q5") (pin "D") (pinfunction "D_D") (pintype "passive"))
      (node (ref "R23") (pin "2") (pinfunction "2_2") (pintype "passive"))
    )
    (net (code "18") (name "/LAYER_5") (class "Default")
      (node (ref "LAYER_1_8") (pin "5") (pinfunction "5_5") (pintype "passive"))
      (node (ref "Q4") (pin "D") (pinfunction "D_D") (pintype "passive"))
      (node (ref "R21") (pin "2") (pinfunction "2_2") (pintype "passive"))
    )
    (net (code "19") (name "/LAYER_6") (class "Default")
      (node (ref "LAYER_1_8") (pin "6") (pinfunction "6_6") (pintype "passive"))
      (node (ref "Q3") (pin "D") (pinfunction "D_D") (pintype "passive"))
      (node (ref "R19") (pin "2") (pinfunction "2_2") (pintype "passive"))
    )
    (net (code "20") (name "/LAYER_7") (class "Default")
      (node (ref "LAYER_1_8") (pin "7") (pinfunction "7_7") (pintype "passive"))
      (node (ref "Q2") (pin "D") (pinfunction "D_D") (pintype "passive"))
      (node (ref "R17") (pin "2") (pinfunction "2_2") (pintype "passive"))
    )
    (net (code "21") (name "/LAYER_8") (class "Default")
      (node (ref "LAYER_1_8") (pin "8") (pinfunction "8_8") (pintype "passive"))
      (node (ref "Q1") (pin "D") (pinfunction "D_D") (pintype "passive"))
      (node (ref "R15") (pin "2") (pinfunction "2_2") (pintype "passive"))
    )
    (net (code "22") (name "/LE_1") (class "Default")
      (node (ref "U1") (pin "4") (pinfunction "LE_4") (pintype "bidirectional"))
      (node (ref "U14") (pin "3") (pinfunction "Y4_3") (pintype "tri_state"))
      (node (ref "U2") (pin "4") (pinfunction "LE_4") (pintype "bidirectional"))
      (node (ref "U3") (pin "4") (pinfunction "LE_4") (pintype "bidirectional"))
      (node (ref "U4") (pin "4") (pinfunction "LE_4") (pintype "bidirectional"))
      (node (ref "U5") (pin "4") (pinfunction "LE_4") (pintype "bidirectional"))
      (node (ref "U6") (pin "4") (pinfunction "LE_4") (pintype "bidirectional"))
      (node (ref "U7") (pin "4") (pinfunction "LE_4") (pintype "bidirectional"))
    )
    (net (code "23") (name "/LE_2") (class "Default")
      (node (ref "U10") (pin "4") (pinfunction "LE_4") (pintype "bidirectional"))
      (node (ref "U11") (pin "4") (pinfunction "LE_4") (pintype "bidirectional"))
      (node (ref "U12") (pin "4") (pinfunction "LE_4") (pintype "bidirectional"))
      (node (ref "U13") (pin "4") (pinfunction "LE_4") (pintype "bidirectional"))
      (node (ref "U14") (pin "14") (pinfunction "Y3_14") (pintype "tri_state"))
      (node (ref "U8") (pin "4") (pinfunction "LE_4") (pintype "bidirectional"))
      (node (ref "U9") (pin "4") (pinfunction "LE_4") (pintype "bidirectional"))
    )
    (net (code "24") (name "/LE_IN") (class "Default")
      (node (ref "CONTROL") (pin "3") (pinfunction "3_3") (pintype "passive"))
      (node (ref "U14") (pin "17") (pinfunction "A4_17") (pintype "input"))
      (node (ref "U14") (pin "6") (pinfunction "A3_6") (pintype "input"))
    )
    (net (code "25") (name "/OE") (class "Default")
      (node (ref "CONTROL") (pin "4") (pinfunction "4_4") (pintype "passive"))
      (node (ref "U1") (pin "21") (pinfunction "OE_21") (pintype "bidirectional"))
      (node (ref "U10") (pin "21") (pinfunction "OE_21") (pintype "bidirectional"))
      (node (ref "U11") (pin "21") (pinfunction "OE_21") (pintype "bidirectional"))
      (node (ref "U12") (pin "21") (pinfunction "OE_21") (pintype "bidirectional"))
      (node (ref "U13") (pin "21") (pinfunction "OE_21") (pintype "bidirectional"))
      (node (ref "U2") (pin "21") (pinfunction "OE_21") (pintype "bidirectional"))
      (node (ref "U3") (pin "21") (pinfunction "OE_21") (pintype "bidirectional"))
      (node (ref "U4") (pin "21") (pinfunction "OE_21") (pintype "bidirectional"))
      (node (ref "U5") (pin "21") (pinfunction "OE_21") (pintype "bidirectional"))
      (node (ref "U6") (pin "21") (pinfunction "OE_21") (pintype "bidirectional"))
      (node (ref "U7") (pin "21") (pinfunction "OE_21") (pintype "bidirectional"))
      (node (ref "U8") (pin "21") (pinfunction "OE_21") (pintype "bidirectional"))
      (node (ref "U9") (pin "21") (pinfunction "OE_21") (pintype "bidirectional"))
    )
    (net (code "26") (name "/SDI_IN") (class "Default")
      (node (ref "CONTROL") (pin "1") (pinfunction "1_1") (pintype "passive"))
      (node (ref "U14") (pin "13") (pinfunction "A2_13") (pintype "input"))
    )
    (net (code "27") (name "/U1_SDI") (class "Default")
      (node (ref "U1") (pin "2") (pinfunction "SDI_2") (pintype "bidirectional"))
      (node (ref "U14") (pin "7") (pinfunction "Y2_7") (pintype "tri_state"))
    )
    (net (code "28") (name "/U5_SDI") (class "Default")
      (node (ref "U4") (pin "22") (pinfunction "SDO_22") (pintype "bidirectional"))
      (node (ref "U5") (pin "2") (pinfunction "SDI_2") (pintype "bidirectional"))
    )
    (net (code "29") (name "/U9_SDI") (class "Default")
      (node (ref "U8") (pin "22") (pinfunction "SDO_22") (pintype "bidirectional"))
      (node (ref "U9") (pin "2") (pinfunction "SDI_2") (pintype "bidirectional"))
    )
    (net (code "30") (name "/U13_SDI") (class "Default")
      (node (ref "U12") (pin "22") (pinfunction "SDO_22") (pintype "bidirectional"))
      (node (ref "U13") (pin "2") (pinfunction "SDI_2") (pintype "bidirectional"))
    )
    (net (code "31") (name "Net-(U1-OUT8)") (class "Default")
      (node (ref "BLUE_1_8") (pin "1") (pinfunction "1_1") (pintype "passive"))
      (node (ref "U1") (pin "13") (pinfunction "OUT8_13") (pintype "bidirectional"))
    )
    (net (code "32") (name "Net-(U1-OUT9)") (class "Default")
      (node (ref "BLUE_1_8") (pin "2") (pinfunction "2_2") (pintype "passive"))
      (node (ref "U1") (pin "14") (pinfunction "OUT9_14") (pintype "bidirectional"))
    )
    (net (code "33") (name "Net-(U1-OUT10)") (class "Default")
      (node (ref "BLUE_1_8") (pin "3") (pinfunction "3_3") (pintype "passive"))
      (node (ref "U1") (pin "15") (pinfunction "OUT10_15") (pintype "bidirectional"))
    )
    (net (code "34") (name "Net-(U1-OUT11)") (class "Default")
      (node (ref "BLUE_1_8") (pin "4") (pinfunction "4_4") (pintype "passive"))
      (node (ref "U1") (pin "16") (pinfunction "OUT11_16") (pintype "bidirectional"))
    )
    (net (code "35") (name "Net-(U1-OUT12)") (class "Default")
      (node (ref "BLUE_1_8") (pin "5") (pinfunction "5_5") (pintype "passive"))
      (node (ref "U1") (pin "17") (pinfunction "OUT12_17") (pintype "bidirectional"))
    )
    (net (code "36") (name "Net-(U1-OUT13)") (class "Default")
      (node (ref "BLUE_1_8") (pin "6") (pinfunction "6_6") (pintype "passive"))
      (node (ref "U1") (pin "18") (pinfunction "OUT13_18") (pintype "bidirectional"))
    )
    (net (code "37") (name "Net-(U1-OUT14)") (class "Default")
      (node (ref "BLUE_1_8") (pin "7") (pinfunction "7_7") (pintype "passive"))
      (node (ref "U1") (pin "19") (pinfunction "OUT14_19") (pintype "bidirectional"))
    )
    (net (code "38") (name "Net-(U1-OUT15)") (class "Default")
      (node (ref "BLUE_1_8") (pin "8") (pinfunction "8_8") (pintype "passive"))
      (node (ref "U1") (pin "20") (pinfunction "OUT15_20") (pintype "bidirectional"))
    )
    (net (code "39") (name "Net-(U1-R-EXT)") (class "Default")
      (node (ref "R1") (pin "2") (pinfunction "2_2") (pintype "passive"))
      (node (ref "U1") (pin "23") (pinfunction "R-EXT_23") (pintype "bidirectional"))
    )
    (net (code "40") (name "Net-(U1-SDO)") (class "Default")
      (node (ref "U1") (pin "22") (pinfunction "SDO_22") (pintype "bidirectional"))
      (node (ref "U2") (pin "2") (pinfunction "SDI_2") (pintype "bidirectional"))
    )
    (net (code "41") (name "Net-(U2-OUT0)") (class "Default")
      (node (ref "BLUE_9_16") (pin "1") (pinfunction "1_1") (pintype "passive"))
      (node (ref "U2") (pin "5") (pinfunction "OUT0_5") (pintype "bidirectional"))
    )
    (net (code "42") (name "Net-(U2-OUT1)") (class "Default")
      (node (ref "BLUE_9_16") (pin "2") (pinfunction "2_2") (pintype "passive"))
      (node (ref "U2") (pin "6") (pinfunction "OUT1_6") (pintype "bidirectional"))
    )
    (net (code "43") (name "Net-(U2-OUT2)") (class "Default")
      (node (ref "BLUE_9_16") (pin "3") (pinfunction "3_3") (pintype "passive"))
      (node (ref "U2") (pin "7") (pinfunction "OUT2_7") (pintype "bidirectional"))
    )
    (net (code "44") (name "Net-(U2-OUT3)") (class "Default")
      (node (ref "BLUE_9_16") (pin "4") (pinfunction "4_4") (pintype "passive"))
      (node (ref "U2") (pin "8") (pinfunction "OUT3_8") (pintype "bidirectional"))
    )
    (net (code "45") (name "Net-(U2-OUT4)") (class "Default")
      (node (ref "BLUE_9_16") (pin "5") (pinfunction "5_5") (pintype "passive"))
      (node (ref "U2") (pin "9") (pinfunction "OUT4_9") (pintype "bidirectional"))
    )
    (net (code "46") (name "Net-(U2-OUT5)") (class "Default")
      (node (ref "BLUE_9_16") (pin "6") (pinfunction "6_6") (pintype "passive"))
      (node (ref "U2") (pin "10") (pinfunction "OUT5_10") (pintype "bidirectional"))
    )
    (net (code "47") (name "Net-(U2-OUT6)") (class "Default")
      (node (ref "BLUE_9_16") (pin "7") (pinfunction "7_7") (pintype "passive"))
      (node (ref "U2") (pin "11") (pinfunction "OUT6_11") (pintype "bidirectional"))
    )
    (net (code "48") (name "Net-(U2-OUT7)") (class "Default")
      (node (ref "BLUE_9_16") (pin "8") (pinfunction "8_8") (pintype "passive"))
      (node (ref "U2") (pin "12") (pinfunction "OUT7_12") (pintype "bidirectional"))
    )
    (net (code "49") (name "Net-(U2-OUT8)") (class "Default")
      (node (ref "BLUE_17_24") (pin "1") (pinfunction "1_1") (pintype "passive"))
      (node (ref "U2") (pin "13") (pinfunction "OUT8_13") (pintype "bidirectional"))
    )
    (net (code "50") (name "Net-(U2-OUT9)") (class "Default")
      (node (ref "BLUE_17_24") (pin "2") (pinfunction "2_2") (pintype "passive"))
      (node (ref "U2") (pin "14") (pinfunction "OUT9_14") (pintype "bidirectional"))
    )
    (net (code "51") (name "Net-(U2-OUT10)") (class "Default")
      (node (ref "BLUE_17_24") (pin "3") (pinfunction "3_3") (pintype "passive"))
      (node (ref "U2") (pin "15") (pinfunction "OUT10_15") (pintype "bidirectional"))
    )
    (net (code "52") (name "Net-(U2-OUT11)") (class "Default")
      (node (ref "BLUE_17_24") (pin "4") (pinfunction "4_4") (pintype "passive"))
      (node (ref "U2") (pin "16") (pinfunction "OUT11_16") (pintype "bidirectional"))
    )
    (net (code "53") (name "Net-(U2-OUT12)") (class "Default")
      (node (ref "BLUE_17_24") (pin "5") (pinfunction "5_5") (pintype "passive"))
      (node (ref "U2") (pin "17") (pinfunction "OUT12_17") (pintype "bidirectional"))
    )
    (net (code "54") (name "Net-(U2-OUT13)") (class "Default")
      (node (ref "BLUE_17_24") (pin "6") (pinfunction "6_6") (pintype "passive"))
      (node (ref "U2") (pin "18") (pinfunction "OUT13_18") (pintype "bidirectional"))
    )
    (net (code "55") (name "Net-(U2-OUT14)") (class "Default")
      (node (ref "BLUE_17_24") (pin "7") (pinfunction "7_7") (pintype "passive"))
      (node (ref "U2") (pin "19") (pinfunction "OUT14_19") (pintype "bidirectional"))
    )
    (net (code "56") (name "Net-(U2-OUT15)") (class "Default")
      (node (ref "BLUE_17_24") (pin "8") (pinfunction "8_8") (pintype "passive"))
      (node (ref "U2") (pin "20") (pinfunction "OUT15_20") (pintype "bidirectional"))
    )
    (net (code "57") (name "Net-(U2-R-EXT)") (class "Default")
      (node (ref "R2") (pin "2") (pinfunction "2_2") (pintype "passive"))
      (node (ref "U2") (pin "23") (pinfunction "R-EXT_23") (pintype "bidirectional"))
    )
    (net (code "58") (name "Net-(U2-SDO)") (class "Default")
      (node (ref "U2") (pin "22") (pinfunction "SDO_22") (pintype "bidirectional"))
      (node (ref "U3") (pin "2") (pinfunction "SDI_2") (pintype "bidirectional"))
    )
    (net (code "59") (name "Net-(U3-OUT0)") (class "Default")
      (node (ref "BLUE_25_32") (pin "1") (pinfunction "1_1") (pintype "passive"))
      (node (ref "U3") (pin "5") (pinfunction "OUT0_5") (pintype "bidirectional"))
    )
    (net (code "60") (name "Net-(U3-OUT1)") (class "Default")
      (node (ref "BLUE_25_32") (pin "2") (pinfunction "2_2") (pintype "passive"))
      (node (ref "U3") (pin "6") (pinfunction "OUT1_6") (pintype "bidirectional"))
    )
    (net (code "61") (name "Net-(U3-OUT2)") (class "Default")
      (node (ref "BLUE_25_32") (pin "3") (pinfunction "3_3") (pintype "passive"))
      (node (ref "U3") (pin "7") (pinfunction "OUT2_7") (pintype "bidirectional"))
    )
    (net (code "62") (name "Net-(U3-OUT3)") (class "Default")
      (node (ref "BLUE_25_32") (pin "4") (pinfunction "4_4") (pintype "passive"))
      (node (ref "U3") (pin "8") (pinfunction "OUT3_8") (pintype "bidirectional"))
    )
    (net (code "63") (name "Net-(U3-OUT4)") (class "Default")
      (node (ref "BLUE_25_32") (pin "5") (pinfunction "5_5") (pintype "passive"))
      (node (ref "U3") (pin "9") (pinfunction "OUT4_9") (pintype "bidirectional"))
    )
    (net (code "64") (name "Net-(U3-OUT5)") (class "Default")
      (node (ref "BLUE_25_32") (pin "6") (pinfunction "6_6") (pintype "passive"))
      (node (ref "U3") (pin "10") (pinfunction "OUT5_10") (pintype "bidirectional"))
    )
    (net (code "65") (name "Net-(U3-OUT6)") (class "Default")
      (node (ref "BLUE_25_32") (pin "7") (pinfunction "7_7") (pintype "passive"))
      (node (ref "U3") (pin "11") (pinfunction "OUT6_11") (pintype "bidirectional"))
    )
    (net (code "66") (name "Net-(U3-OUT7)") (class "Default")
      (node (ref "BLUE_25_32") (pin "8") (pinfunction "8_8") (pintype "passive"))
      (node (ref "U3") (pin "12") (pinfunction "OUT7_12") (pintype "bidirectional"))
    )
    (net (code "67") (name "Net-(U3-OUT8)") (class "Default")
      (node (ref "BLUE_33_40") (pin "1") (pinfunction "1_1") (pintype "passive"))
      (node (ref "U3") (pin "13") (pinfunction "OUT8_13") (pintype "bidirectional"))
    )
    (net (code "68") (name "Net-(U3-OUT9)") (class "Default")
      (node (ref "BLUE_33_40") (pin "2") (pinfunction "2_2") (pintype "passive"))
      (node (ref "U3") (pin "14") (pinfunction "OUT9_14") (pintype "bidirectional"))
    )
    (net (code "69") (name "Net-(U3-OUT10)") (class "Default")
      (node (ref "BLUE_33_40") (pin "3") (pinfunction "3_3") (pintype "passive"))
      (node (ref "U3") (pin "15") (pinfunction "OUT10_15") (pintype "bidirectional"))
    )
    (net (code "70") (name "Net-(U3-OUT11)") (class "Default")
      (node (ref "BLUE_33_40") (pin "4") (pinfunction "4_4") (pintype "passive"))
      (node (ref "U3") (pin "16") (pinfunction "OUT11_16") (pintype "bidirectional"))
    )
    (net (code "71") (name "Net-(U3-OUT12)") (class "Default")
      (node (ref "BLUE_33_40") (pin "5") (pinfunction "5_5") (pintype "passive"))
      (node (ref "U3") (pin "17") (pinfunction "OUT12_17") (pintype "bidirectional"))
    )
    (net (code "72") (name "Net-(U3-OUT13)") (class "Default")
      (node (ref "BLUE_33_40") (pin "6") (pinfunction "6_6") (pintype "passive"))
      (node (ref "U3") (pin "18") (pinfunction "OUT13_18") (pintype "bidirectional"))
    )
    (net (code "73") (name "Net-(U3-OUT14)") (class "Default")
      (node (ref "BLUE_33_40") (pin "7") (pinfunction "7_7") (pintype "passive"))
      (node (ref "U3") (pin "19") (pinfunction "OUT14_19") (pintype "bidirectional"))
    )
    (net (code "74") (name "Net-(U3-OUT15)") (class "Default")
      (node (ref "BLUE_33_40") (pin "8") (pinfunction "8_8") (pintype "passive"))
      (node (ref "U3") (pin "20") (pinfunction "OUT15_20") (pintype "bidirectional"))
    )
    (net (code "75") (name "Net-(U3-R-EXT)") (class "Default")
      (node (ref "R3") (pin "2") (pinfunction "2_2") (pintype "passive"))
      (node (ref "U3") (pin "23") (pinfunction "R-EXT_23") (pintype "bidirectional"))
    )
    (net (code "76") (name "Net-(U3-SDO)") (class "Default")
      (node (ref "U3") (pin "22") (pinfunction "SDO_22") (pintype "bidirectional"))
      (node (ref "U4") (pin "2") (pinfunction "SDI_2") (pintype "bidirectional"))
    )
    (net (code "77") (name "Net-(U4-OUT0)") (class "Default")
      (node (ref "BLUE_41_48") (pin "1") (pinfunction "1_1") (pintype "passive"))
      (node (ref "U4") (pin "5") (pinfunction "OUT0_5") (pintype "bidirectional"))
    )
    (net (code "78") (name "Net-(U4-OUT1)") (class "Default")
      (node (ref "BLUE_41_48") (pin "2") (pinfunction "2_2") (pintype "passive"))
      (node (ref "U4") (pin "6") (pinfunction "OUT1_6") (pintype "bidirectional"))
    )
    (net (code "79") (name "Net-(U4-OUT2)") (class "Default")
      (node (ref "BLUE_41_48") (pin "3") (pinfunction "3_3") (pintype "passive"))
      (node (ref "U4") (pin "7") (pinfunction "OUT2_7") (pintype "bidirectional"))
    )
    (net (code "80") (name "Net-(U4-OUT3)") (class "Default")
      (node (ref "BLUE_41_48") (pin "4") (pinfunction "4_4") (pintype "passive"))
      (node (ref "U4") (pin "8") (pinfunction "OUT3_8") (pintype "bidirectional"))
    )
    (net (code "81") (name "Net-(U4-OUT4)") (class "Default")
      (node (ref "BLUE_41_48") (pin "5") (pinfunction "5_5") (pintype "passive"))
      (node (ref "U4") (pin "9") (pinfunction "OUT4_9") (pintype "bidirectional"))
    )
    (net (code "82") (name "Net-(U4-OUT5)") (class "Default")
      (node (ref "BLUE_41_48") (pin "6") (pinfunction "6_6") (pintype "passive"))
      (node (ref "U4") (pin "10") (pinfunction "OUT5_10") (pintype "bidirectional"))
    )
    (net (code "83") (name "Net-(U4-OUT6)") (class "Default")
      (node (ref "BLUE_41_48") (pin "7") (pinfunction "7_7") (pintype "passive"))
      (node (ref "U4") (pin "11") (pinfunction "OUT6_11") (pintype "bidirectional"))
    )
    (net (code "84") (name "Net-(U4-OUT7)") (class "Default")
      (node (ref "BLUE_41_48") (pin "8") (pinfunction "8_8") (pintype "passive"))
      (node (ref "U4") (pin "12") (pinfunction "OUT7_12") (pintype "bidirectional"))
    )
    (net (code "85") (name "Net-(U4-OUT8)") (class "Default")
      (node (ref "BLUE_49_56") (pin "1") (pinfunction "1_1") (pintype "passive"))
      (node (ref "U4") (pin "13") (pinfunction "OUT8_13") (pintype "bidirectional"))
    )
    (net (code "86") (name "Net-(U4-OUT9)") (class "Default")
      (node (ref "BLUE_49_56") (pin "2") (pinfunction "2_2") (pintype "passive"))
      (node (ref "U4") (pin "14") (pinfunction "OUT9_14") (pintype "bidirectional"))
    )
    (net (code "87") (name "Net-(U4-OUT10)") (class "Default")
      (node (ref "BLUE_49_56") (pin "3") (pinfunction "3_3") (pintype "passive"))
      (node (ref "U4") (pin "15") (pinfunction "OUT10_15") (pintype "bidirectional"))
    )
    (net (code "88") (name "Net-(U4-OUT11)") (class "Default")
      (node (ref "BLUE_49_56") (pin "4") (pinfunction "4_4") (pintype "passive"))
      (node (ref "U4") (pin "16") (pinfunction "OUT11_16") (pintype "bidirectional"))
    )
    (net (code "89") (name "Net-(U4-OUT12)") (class "Default")
      (node (ref "BLUE_49_56") (pin "5") (pinfunction "5_5") (pintype "passive"))
      (node (ref "U4") (pin "17") (pinfunction "OUT12_17") (pintype "bidirectional"))
    )
    (net (code "90") (name "Net-(U4-OUT13)") (class "Default")
      (node (ref "BLUE_49_56") (pin "6") (pinfunction "6_6") (pintype "passive"))
      (node (ref "U4") (pin "18") (pinfunction "OUT13_18") (pintype "bidirectional"))
    )
    (net (code "91") (name "Net-(U4-OUT14)") (class "Default")
      (node (ref "BLUE_49_56") (pin "7") (pinfunction "7_7") (pintype "passive"))
      (node (ref "U4") (pin "19") (pinfunction "OUT14_19") (pintype "bidirectional"))
    )
    (net (code "92") (name "Net-(U4-OUT15)") (class "Default")
      (node (ref "BLUE_49_56") (pin "8") (pinfunction "8_8") (pintype "passive"))
      (node (ref "U4") (pin "20") (pinfunction "OUT15_20") (pintype "bidirectional"))
    )
    (net (code "93") (name "Net-(U4-R-EXT)") (class "Default")
      (node (ref "R4") (pin "2") (pinfunction "2_2") (pintype "passive"))
      (node (ref "U4") (pin "23") (pinfunction "R-EXT_23") (pintype "bidirectional"))
    )
    (net (code "94") (name "Net-(U5-OUT0)") (class "Default")
      (node (ref "BLUE_57_64") (pin "1") (pinfunction "1_1") (pintype "passive"))
      (node (ref "U5") (pin "5") (pinfunction "OUT0_5") (pintype "bidirectional"))
    )
    (net (code "95") (name "Net-(U5-OUT1)") (class "Default")
      (node (ref "BLUE_57_64") (pin "2") (pinfunction "2_2") (pintype "passive"))
      (node (ref "U5") (pin "6") (pinfunction "OUT1_6") (pintype "bidirectional"))
    )
    (net (code "96") (name "Net-(U5-OUT2)") (class "Default")
      (node (ref "BLUE_57_64") (pin "3") (pinfunction "3_3") (pintype "passive"))
      (node (ref "U5") (pin "7") (pinfunction "OUT2_7") (pintype "bidirectional"))
    )
    (net (code "97") (name "Net-(U5-OUT3)") (class "Default")
      (node (ref "BLUE_57_64") (pin "4") (pinfunction "4_4") (pintype "passive"))
      (node (ref "U5") (pin "8") (pinfunction "OUT3_8") (pintype "bidirectional"))
    )
    (net (code "98") (name "Net-(U5-OUT4)") (class "Default")
      (node (ref "BLUE_57_64") (pin "5") (pinfunction "5_5") (pintype "passive"))
      (node (ref "U5") (pin "9") (pinfunction "OUT4_9") (pintype "bidirectional"))
    )
    (net (code "99") (name "Net-(U5-OUT5)") (class "Default")
      (node (ref "BLUE_57_64") (pin "6") (pinfunction "6_6") (pintype "passive"))
      (node (ref "U5") (pin "10") (pinfunction "OUT5_10") (pintype "bidirectional"))
    )
    (net (code "100") (name "Net-(U5-OUT6)") (class "Default")
      (node (ref "BLUE_57_64") (pin "7") (pinfunction "7_7") (pintype "passive"))
      (node (ref "U5") (pin "11") (pinfunction "OUT6_11") (pintype "bidirectional"))
    )
    (net (code "101") (name "Net-(U5-OUT7)") (class "Default")
      (node (ref "BLUE_57_64") (pin "8") (pinfunction "8_8") (pintype "passive"))
      (node (ref "U5") (pin "12") (pinfunction "OUT7_12") (pintype "bidirectional"))
    )
    (net (code "102") (name "Net-(U5-OUT8)") (class "Default")
      (node (ref "GREEN_1_8") (pin "1") (pinfunction "1_1") (pintype "passive"))
      (node (ref "U5") (pin "13") (pinfunction "OUT8_13") (pintype "bidirectional"))
    )
    (net (code "103") (name "Net-(U5-OUT9)") (class "Default")
      (node (ref "GREEN_1_8") (pin "2") (pinfunction "2_2") (pintype "passive"))
      (node (ref "U5") (pin "14") (pinfunction "OUT9_14") (pintype "bidirectional"))
    )
    (net (code "104") (name "Net-(U5-OUT10)") (class "Default")
      (node (ref "GREEN_1_8") (pin "3") (pinfunction "3_3") (pintype "passive"))
      (node (ref "U5") (pin "15") (pinfunction "OUT10_15") (pintype "bidirectional"))
    )
    (net (code "105") (name "Net-(U5-OUT11)") (class "Default")
      (node (ref "GREEN_1_8") (pin "4") (pinfunction "4_4") (pintype "passive"))
      (node (ref "U5") (pin "16") (pinfunction "OUT11_16") (pintype "bidirectional"))
    )
    (net (code "106") (name "Net-(U5-OUT12)") (class "Default")
      (node (ref "GREEN_1_8") (pin "5") (pinfunction "5_5") (pintype "passive"))
      (node (ref "U5") (pin "17") (pinfunction "OUT12_17") (pintype "bidirectional"))
    )
    (net (code "107") (name "Net-(U5-OUT13)") (class "Default")
      (node (ref "GREEN_1_8") (pin "6") (pinfunction "6_6") (pintype "passive"))
      (node (ref "U5") (pin "18") (pinfunction "OUT13_18") (pintype "bidirectional"))
    )
    (net (code "108") (name "Net-(U5-OUT14)") (class "Default")
      (node (ref "GREEN_1_8") (pin "7") (pinfunction "7_7") (pintype "passive"))
      (node (ref "U5") (pin "19") (pinfunction "OUT14_19") (pintype "bidirectional"))
    )
    (net (code "109") (name "Net-(U5-OUT15)") (class "Default")
      (node (ref "GREEN_1_8") (pin "8") (pinfunction "8_8") (pintype "passive"))
      (node (ref "U5") (pin "20") (pinfunction "OUT15_20") (pintype "bidirectional"))
    )
    (net (code "110") (name "Net-(U5-R-EXT)") (class "Default")
      (node (ref "R5") (pin "2") (pinfunction "2_2") (pintype "passive"))
      (node (ref "U5") (pin "23") (pinfunction "R-EXT_23") (pintype "bidirectional"))
    )
    (net (code "111") (name "Net-(U5-SDO)") (class "Default")
      (node (ref "U5") (pin "22") (pinfunction "SDO_22") (pintype "bidirectional"))
      (node (ref "U6") (pin "2") (pinfunction "SDI_2") (pintype "bidirectional"))
    )
    (net (code "112") (name "Net-(U6-OUT0)") (class "Default")
      (node (ref "GREEN_9_16") (pin "1") (pinfunction "1_1") (pintype "passive"))
      (node (ref "U6") (pin "5") (pinfunction "OUT0_5") (pintype "bidirectional"))
    )
    (net (code "113") (name "Net-(U6-OUT1)") (class "Default")
      (node (ref "GREEN_9_16") (pin "2") (pinfunction "2_2") (pintype "passive"))
      (node (ref "U6") (pin "6") (pinfunction "OUT1_6") (pintype "bidirectional"))
    )
    (net (code "114") (name "Net-(U6-OUT2)") (class "Default")
      (node (ref "GREEN_9_16") (pin "3") (pinfunction "3_3") (pintype "passive"))
      (node (ref "U6") (pin "7") (pinfunction "OUT2_7") (pintype "bidirectional"))
    )
    (net (code "115") (name "Net-(U6-OUT3)") (class "Default")
      (node (ref "GREEN_9_16") (pin "4") (pinfunction "4_4") (pintype "passive"))
      (node (ref "U6") (pin "8") (pinfunction "OUT3_8") (pintype "bidirectional"))
    )
    (net (code "116") (name "Net-(U6-OUT4)") (class "Default")
      (node (ref "GREEN_9_16") (pin "5") (pinfunction "5_5") (pintype "passive"))
      (node (ref "U6") (pin "9") (pinfunction "OUT4_9") (pintype "bidirectional"))
    )
    (net (code "117") (name "Net-(U6-OUT5)") (class "Default")
      (node (ref "GREEN_9_16") (pin "6") (pinfunction "6_6") (pintype "passive"))
      (node (ref "U6") (pin "10") (pinfunction "OUT5_10") (pintype "bidirectional"))
    )
    (net (code "118") (name "Net-(U6-OUT6)") (class "Default")
      (node (ref "GREEN_9_16") (pin "7") (pinfunction "7_7") (pintype "passive"))
      (node (ref "U6") (pin "11") (pinfunction "OUT6_11") (pintype "bidirectional"))
    )
    (net (code "119") (name "Net-(U6-OUT7)") (class "Default")
      (node (ref "GREEN_9_16") (pin "8") (pinfunction "8_8") (pintype "passive"))
      (node (ref "U6") (pin "12") (pinfunction "OUT7_12") (pintype "bidirectional"))
    )
    (net (code "120") (name "Net-(U6-OUT8)") (class "Default")
      (node (ref "GREEN_17_24") (pin "1") (pinfunction "1_1") (pintype "passive"))
      (node (ref "U6") (pin "13") (pinfunction "OUT8_13") (pintype "bidirectional"))
    )
    (net (code "121") (name "Net-(U6-OUT9)") (class "Default")
      (node (ref "GREEN_17_24") (pin "2") (pinfunction "2_2") (pintype "passive"))
      (node (ref "U6") (pin "14") (pinfunction "OUT9_14") (pintype "bidirectional"))
    )
    (net (code "122") (name "Net-(U6-OUT10)") (class "Default")
      (node (ref "GREEN_17_24") (pin "3") (pinfunction "3_3") (pintype "passive"))
      (node (ref "U6") (pin "15") (pinfunction "OUT10_15") (pintype "bidirectional"))
    )
    (net (code "123") (name "Net-(U6-OUT11)") (class "Default")
      (node (ref "GREEN_17_24") (pin "4") (pinfunction "4_4") (pintype "passive"))
      (node (ref "U6") (pin "16") (pinfunction "OUT11_16") (pintype "bidirectional"))
    )
    (net (code "124") (name "Net-(U6-OUT12)") (class "Default")
      (node (ref "GREEN_17_24") (pin "5") (pinfunction "5_5") (pintype "passive"))
      (node (ref "U6") (pin "17") (pinfunction "OUT12_17") (pintype "bidirectional"))
    )
    (net (code "125") (name "Net-(U6-OUT13)") (class "Default")
      (node (ref "GREEN_17_24") (pin "6") (pinfunction "6_6") (pintype "passive"))
      (node (ref "U6") (pin "18") (pinfunction "OUT13_18") (pintype "bidirectional"))
    )
    (net (code "126") (name "Net-(U6-OUT14)") (class "Default")
      (node (ref "GREEN_17_24") (pin "7") (pinfunction "7_7") (pintype "passive"))
      (node (ref "U6") (pin "19") (pinfunction "OUT14_19") (pintype "bidirectional"))
    )
    (net (code "127") (name "Net-(U6-OUT15)") (class "Default")
      (node (ref "GREEN_17_24") (pin "8") (pinfunction "8_8") (pintype "passive"))
      (node (ref "U6") (pin "20") (pinfunction "OUT15_20") (pintype "bidirectional"))
    )
    (net (code "128") (name "Net-(U6-R-EXT)") (class "Default")
      (node (ref "R6") (pin "2") (pinfunction "2_2") (pintype "passive"))
      (node (ref "U6") (pin "23") (pinfunction "R-EXT_23") (pintype "bidirectional"))
    )
    (net (code "129") (name "Net-(U6-SDO)") (class "Default")
      (node (ref "U6") (pin "22") (pinfunction "SDO_22") (pintype "bidirectional"))
      (node (ref "U7") (pin "2") (pinfunction "SDI_2") (pintype "bidirectional"))
    )
    (net (code "130") (name "Net-(U7-OUT0)") (class "Default")
      (node (ref "GREEN_25_32") (pin "1") (pinfunction "1_1") (pintype "passive"))
      (node (ref "U7") (pin "5") (pinfunction "OUT0_5") (pintype "bidirectional"))
    )
    (net (code "131") (name "Net-(U7-OUT1)") (class "Default")
      (node (ref "GREEN_25_32") (pin "2") (pinfunction "2_2") (pintype "passive"))
      (node (ref "U7") (pin "6") (pinfunction "OUT1_6") (pintype "bidirectional"))
    )
    (net (code "132") (name "Net-(U7-OUT2)") (class "Default")
      (node (ref "GREEN_25_32") (pin "3") (pinfunction "3_3") (pintype "passive"))
      (node (ref "U7") (pin "7") (pinfunction "OUT2_7") (pintype "bidirectional"))
    )
    (net (code "133") (name "Net-(U7-OUT3)") (class "Default")
      (node (ref "GREEN_25_32") (pin "4") (pinfunction "4_4") (pintype "passive"))
      (node (ref "U7") (pin "8") (pinfunction "OUT3_8") (pintype "bidirectional"))
    )
    (net (code "134") (name "Net-(U7-OUT4)") (class "Default")
      (node (ref "GREEN_25_32") (pin "5") (pinfunction "5_5") (pintype "passive"))
      (node (ref "U7") (pin "9") (pinfunction "OUT4_9") (pintype "bidirectional"))
    )
    (net (code "135") (name "Net-(U7-OUT5)") (class "Default")
      (node (ref "GREEN_25_32") (pin "6") (pinfunction "6_6") (pintype "passive"))
      (node (ref "U7") (pin "10") (pinfunction "OUT5_10") (pintype "bidirectional"))
    )
    (net (code "136") (name "Net-(U7-OUT6)") (class "Default")
      (node (ref "GREEN_25_32") (pin "7") (pinfunction "7_7") (pintype "passive"))
      (node (ref "U7") (pin "11") (pinfunction "OUT6_11") (pintype "bidirectional"))
    )
    (net (code "137") (name "Net-(U7-OUT7)") (class "Default")
      (node (ref "GREEN_25_32") (pin "8") (pinfunction "8_8") (pintype "passive"))
      (node (ref "U7") (pin "12") (pinfunction "OUT7_12") (pintype "bidirectional"))
    )
    (net (code "138") (name "Net-(U7-OUT8)") (class "Default")
      (node (ref "GREEN_33_40") (pin "1") (pinfunction "1_1") (pintype "passive"))
      (node (ref "U7") (pin "13") (pinfunction "OUT8_13") (pintype "bidirectional"))
    )
    (net (code "139") (name "Net-(U7-OUT9)") (class "Default")
      (node (ref "GREEN_33_40") (pin "2") (pinfunction "2_2") (pintype "passive"))
      (node (ref "U7") (pin "14") (pinfunction "OUT9_14") (pintype "bidirectional"))
    )
    (net (code "140") (name "Net-(U7-OUT10)") (class "Default")
      (node (ref "GREEN_33_40") (pin "3") (pinfunction "3_3") (pintype "passive"))
      (node (ref "U7") (pin "15") (pinfunction "OUT10_15") (pintype "bidirectional"))
    )
    (net (code "141") (name "Net-(U7-OUT11)") (class "Default")
      (node (ref "GREEN_33_40") (pin "4") (pinfunction "4_4") (pintype "passive"))
      (node (ref "U7") (pin "16") (pinfunction "OUT11_16") (pintype "bidirectional"))
    )
    (net (code "142") (name "Net-(U7-OUT12)") (class "Default")
      (node (ref "GREEN_33_40") (pin "5") (pinfunction "5_5") (pintype "passive"))
      (node (ref "U7") (pin "17") (pinfunction "OUT12_17") (pintype "bidirectional"))
    )
    (net (code "143") (name "Net-(U7-OUT13)") (class "Default")
      (node (ref "GREEN_33_40") (pin "6") (pinfunction "6_6") (pintype "passive"))
      (node (ref "U7") (pin "18") (pinfunction "OUT13_18") (pintype "bidirectional"))
    )
    (net (code "144") (name "Net-(U7-OUT14)") (class "Default")
      (node (ref "GREEN_33_40") (pin "7") (pinfunction "7_7") (pintype "passive"))
      (node (ref "U7") (pin "19") (pinfunction "OUT14_19") (pintype "bidirectional"))
    )
    (net (code "145") (name "Net-(U7-OUT15)") (class "Default")
      (node (ref "GREEN_33_40") (pin "8") (pinfunction "8_8") (pintype "passive"))
      (node (ref "U7") (pin "20") (pinfunction "OUT15_20") (pintype "bidirectional"))
    )
    (net (code "146") (name "Net-(U7-R-EXT)") (class "Default")
      (node (ref "R7") (pin "2") (pinfunction "2_2") (pintype "passive"))
      (node (ref "U7") (pin "23") (pinfunction "R-EXT_23") (pintype "bidirectional"))
    )
    (net (code "147") (name "Net-(U7-SDO)") (class "Default")
      (node (ref "U7") (pin "22") (pinfunction "SDO_22") (pintype "bidirectional"))
      (node (ref "U8") (pin "2") (pinfunction "SDI_2") (pintype "bidirectional"))
    )
    (net (code "148") (name "Net-(U8-OUT0)") (class "Default")
      (node (ref "GREEN_41_48") (pin "1") (pinfunction "1_1") (pintype "passive"))
      (node (ref "U8") (pin "5") (pinfunction "OUT0_5") (pintype "bidirectional"))
    )
    (net (code "149") (name "Net-(U8-OUT1)") (class "Default")
      (node (ref "GREEN_41_48") (pin "2") (pinfunction "2_2") (pintype "passive"))
      (node (ref "U8") (pin "6") (pinfunction "OUT1_6") (pintype "bidirectional"))
    )
    (net (code "150") (name "Net-(U8-OUT2)") (class "Default")
      (node (ref "GREEN_41_48") (pin "3") (pinfunction "3_3") (pintype "passive"))
      (node (ref "U8") (pin "7") (pinfunction "OUT2_7") (pintype "bidirectional"))
    )
    (net (code "151") (name "Net-(U8-OUT3)") (class "Default")
      (node (ref "GREEN_41_48") (pin "4") (pinfunction "4_4") (pintype "passive"))
      (node (ref "U8") (pin "8") (pinfunction "OUT3_8") (pintype "bidirectional"))
    )
    (net (code "152") (name "Net-(U8-OUT4)") (class "Default")
      (node (ref "GREEN_41_48") (pin "5") (pinfunction "5_5") (pintype "passive"))
      (node (ref "U8") (pin "9") (pinfunction "OUT4_9") (pintype "bidirectional"))
    )
    (net (code "153") (name "Net-(U8-OUT5)") (class "Default")
      (node (ref "GREEN_41_48") (pin "6") (pinfunction "6_6") (pintype "passive"))
      (node (ref "U8") (pin "10") (pinfunction "OUT5_10") (pintype "bidirectional"))
    )
    (net (code "154") (name "Net-(U8-OUT6)") (class "Default")
      (node (ref "GREEN_41_48") (pin "7") (pinfunction "7_7") (pintype "passive"))
      (node (ref "U8") (pin "11") (pinfunction "OUT6_11") (pintype "bidirectional"))
    )
    (net (code "155") (name "Net-(U8-OUT7)") (class "Default")
      (node (ref "GREEN_41_48") (pin "8") (pinfunction "8_8") (pintype "passive"))
      (node (ref "U8") (pin "12") (pinfunction "OUT7_12") (pintype "bidirectional"))
    )
    (net (code "156") (name "Net-(U8-OUT8)") (class "Default")
      (node (ref "GREEN_49_56") (pin "1") (pinfunction "1_1") (pintype "passive"))
      (node (ref "U8") (pin "13") (pinfunction "OUT8_13") (pintype "bidirectional"))
    )
    (net (code "157") (name "Net-(U8-OUT9)") (class "Default")
      (node (ref "GREEN_49_56") (pin "2") (pinfunction "2_2") (pintype "passive"))
      (node (ref "U8") (pin "14") (pinfunction "OUT9_14") (pintype "bidirectional"))
    )
    (net (code "158") (name "Net-(U8-OUT10)") (class "Default")
      (node (ref "GREEN_49_56") (pin "3") (pinfunction "3_3") (pintype "passive"))
      (node (ref "U8") (pin "15") (pinfunction "OUT10_15") (pintype "bidirectional"))
    )
    (net (code "159") (name "Net-(U8-OUT11)") (class "Default")
      (node (ref "GREEN_49_56") (pin "4") (pinfunction "4_4") (pintype "passive"))
      (node (ref "U8") (pin "16") (pinfunction "OUT11_16") (pintype "bidirectional"))
    )
    (net (code "160") (name "Net-(U8-OUT12)") (class "Default")
      (node (ref "GREEN_49_56") (pin "5") (pinfunction "5_5") (pintype "passive"))
      (node (ref "U8") (pin "17") (pinfunction "OUT12_17") (pintype "bidirectional"))
    )
    (net (code "161") (name "Net-(U8-OUT13)") (class "Default")
      (node (ref "GREEN_49_56") (pin "6") (pinfunction "6_6") (pintype "passive"))
      (node (ref "U8") (pin "18") (pinfunction "OUT13_18") (pintype "bidirectional"))
    )
    (net (code "162") (name "Net-(U8-OUT14)") (class "Default")
      (node (ref "GREEN_49_56") (pin "7") (pinfunction "7_7") (pintype "passive"))
      (node (ref "U8") (pin "19") (pinfunction "OUT14_19") (pintype "bidirectional"))
    )
    (net (code "163") (name "Net-(U8-OUT15)") (class "Default")
      (node (ref "GREEN_49_56") (pin "8") (pinfunction "8_8") (pintype "passive"))
      (node (ref "U8") (pin "20") (pinfunction "OUT15_20") (pintype "bidirectional"))
    )
    (net (code "164") (name "Net-(U8-R-EXT)") (class "Default")
      (node (ref "R8") (pin "2") (pinfunction "2_2") (pintype "passive"))
      (node (ref "U8") (pin "23") (pinfunction "R-EXT_23") (pintype "bidirectional"))
    )
    (net (code "165") (name "Net-(U9-OUT0)") (class "Default")
      (node (ref "GREEN_57_64") (pin "1") (pinfunction "1_1") (pintype "passive"))
      (node (ref "U9") (pin "5") (pinfunction "OUT0_5") (pintype "bidirectional"))
    )
    (net (code "166") (name "Net-(U9-OUT1)") (class "Default")
      (node (ref "GREEN_57_64") (pin "2") (pinfunction "2_2") (pintype "passive"))
      (node (ref "U9") (pin "6") (pinfunction "OUT1_6") (pintype "bidirectional"))
    )
    (net (code "167") (name "Net-(U9-OUT2)") (class "Default")
      (node (ref "GREEN_57_64") (pin "3") (pinfunction "3_3") (pintype "passive"))
      (node (ref "U9") (pin "7") (pinfunction "OUT2_7") (pintype "bidirectional"))
    )
    (net (code "168") (name "Net-(U9-OUT3)") (class "Default")
      (node (ref "GREEN_57_64") (pin "4") (pinfunction "4_4") (pintype "passive"))
      (node (ref "U9") (pin "8") (pinfunction "OUT3_8") (pintype "bidirectional"))
    )
    (net (code "169") (name "Net-(U9-OUT4)") (class "Default")
      (node (ref "GREEN_57_64") (pin "5") (pinfunction "5_5") (pintype "passive"))
      (node (ref "U9") (pin "9") (pinfunction "OUT4_9") (pintype "bidirectional"))
    )
    (net (code "170") (name "Net-(U9-OUT5)") (class "Default")
      (node (ref "GREEN_57_64") (pin "6") (pinfunction "6_6") (pintype "passive"))
      (node (ref "U9") (pin "10") (pinfunction "OUT5_10") (pintype "bidirectional"))
    )
    (net (code "171") (name "Net-(U9-OUT6)") (class "Default")
      (node (ref "GREEN_57_64") (pin "7") (pinfunction "7_7") (pintype "passive"))
      (node (ref "U9") (pin "11") (pinfunction "OUT6_11") (pintype "bidirectional"))
    )
    (net (code "172") (name "Net-(U9-OUT7)") (class "Default")
      (node (ref "GREEN_57_64") (pin "8") (pinfunction "8_8") (pintype "passive"))
      (node (ref "U9") (pin "12") (pinfunction "OUT7_12") (pintype "bidirectional"))
    )
    (net (code "173") (name "Net-(U9-OUT8)") (class "Default")
      (node (ref "RED_1_8") (pin "1") (pinfunction "1_1") (pintype "passive"))
      (node (ref "U9") (pin "13") (pinfunction "OUT8_13") (pintype "bidirectional"))
    )
    (net (code "174") (name "Net-(U9-OUT9)") (class "Default")
      (node (ref "RED_1_8") (pin "2") (pinfunction "2_2") (pintype "passive"))
      (node (ref "U9") (pin "14") (pinfunction "OUT9_14") (pintype "bidirectional"))
    )
    (net (code "175") (name "Net-(U9-OUT10)") (class "Default")
      (node (ref "RED_1_8") (pin "3") (pinfunction "3_3") (pintype "passive"))
      (node (ref "U9") (pin "15") (pinfunction "OUT10_15") (pintype "bidirectional"))
    )
    (net (code "176") (name "Net-(U9-OUT11)") (class "Default")
      (node (ref "RED_1_8") (pin "4") (pinfunction "4_4") (pintype "passive"))
      (node (ref "U9") (pin "16") (pinfunction "OUT11_16") (pintype "bidirectional"))
    )
    (net (code "177") (name "Net-(U9-OUT12)") (class "Default")
      (node (ref "RED_1_8") (pin "5") (pinfunction "5_5") (pintype "passive"))
      (node (ref "U9") (pin "17") (pinfunction "OUT12_17") (pintype "bidirectional"))
    )
    (net (code "178") (name "Net-(U9-OUT13)") (class "Default")
      (node (ref "RED_1_8") (pin "6") (pinfunction "6_6") (pintype "passive"))
      (node (ref "U9") (pin "18") (pinfunction "OUT13_18") (pintype "bidirectional"))
    )
    (net (code "179") (name "Net-(U9-OUT14)") (class "Default")
      (node (ref "RED_1_8") (pin "7") (pinfunction "7_7") (pintype "passive"))
      (node (ref "U9") (pin "19") (pinfunction "OUT14_19") (pintype "bidirectional"))
    )
    (net (code "180") (name "Net-(U9-OUT15)") (class "Default")
      (node (ref "RED_1_8") (pin "8") (pinfunction "8_8") (pintype "passive"))
      (node (ref "U9") (pin "20") (pinfunction "OUT15_20") (pintype "bidirectional"))
    )
    (net (code "181") (name "Net-(U9-R-EXT)") (class "Default")
      (node (ref "R9") (pin "2") (pinfunction "2_2") (pintype "passive"))
      (node (ref "U9") (pin "23") (pinfunction "R-EXT_23") (pintype "bidirectional"))
    )
    (net (code "182") (name "Net-(U10-OUT0)") (class "Default")
      (node (ref "RED_9_16") (pin "1") (pinfunction "1_1") (pintype "passive"))
      (node (ref "U10") (pin "5") (pinfunction "OUT0_5") (pintype "bidirectional"))
    )
    (net (code "183") (name "Net-(U10-OUT1)") (class "Default")
      (node (ref "RED_9_16") (pin "2") (pinfunction "2_2") (pintype "passive"))
      (node (ref "U10") (pin "6") (pinfunction "OUT1_6") (pintype "bidirectional"))
    )
    (net (code "184") (name "Net-(U10-OUT2)") (class "Default")
      (node (ref "RED_9_16") (pin "3") (pinfunction "3_3") (pintype "passive"))
      (node (ref "U10") (pin "7") (pinfunction "OUT2_7") (pintype "bidirectional"))
    )
    (net (code "185") (name "Net-(U10-OUT3)") (class "Default")
      (node (ref "RED_9_16") (pin "4") (pinfunction "4_4") (pintype "passive"))
      (node (ref "U10") (pin "8") (pinfunction "OUT3_8") (pintype "bidirectional"))
    )
    (net (code "186") (name "Net-(U10-OUT4)") (class "Default")
      (node (ref "RED_9_16") (pin "5") (pinfunction "5_5") (pintype "passive"))
      (node (ref "U10") (pin "9") (pinfunction "OUT4_9") (pintype "bidirectional"))
    )
    (net (code "187") (name "Net-(U10-OUT5)") (class "Default")
      (node (ref "RED_9_16") (pin "6") (pinfunction "6_6") (pintype "passive"))
      (node (ref "U10") (pin "10") (pinfunction "OUT5_10") (pintype "bidirectional"))
    )
    (net (code "188") (name "Net-(U10-OUT6)") (class "Default")
      (node (ref "RED_9_16") (pin "7") (pinfunction "7_7") (pintype "passive"))
      (node (ref "U10") (pin "11") (pinfunction "OUT6_11") (pintype "bidirectional"))
    )
    (net (code "189") (name "Net-(U10-OUT7)") (class "Default")
      (node (ref "RED_9_16") (pin "8") (pinfunction "8_8") (pintype "passive"))
      (node (ref "U10") (pin "12") (pinfunction "OUT7_12") (pintype "bidirectional"))
    )
    (net (code "190") (name "Net-(U10-OUT8)") (class "Default")
      (node (ref "RED_17_24") (pin "1") (pinfunction "1_1") (pintype "passive"))
      (node (ref "U10") (pin "13") (pinfunction "OUT8_13") (pintype "bidirectional"))
    )
    (net (code "191") (name "Net-(U10-OUT9)") (class "Default")
      (node (ref "RED_17_24") (pin "2") (pinfunction "2_2") (pintype "passive"))
      (node (ref "U10") (pin "14") (pinfunction "OUT9_14") (pintype "bidirectional"))
    )
    (net (code "192") (name "Net-(U10-OUT10)") (class "Default")
      (node (ref "RED_17_24") (pin "3") (pinfunction "3_3") (pintype "passive"))
      (node (ref "U10") (pin "15") (pinfunction "OUT10_15") (pintype "bidirectional"))
    )
    (net (code "193") (name "Net-(U10-OUT11)") (class "Default")
      (node (ref "RED_17_24") (pin "4") (pinfunction "4_4") (pintype "passive"))
      (node (ref "U10") (pin "16") (pinfunction "OUT11_16") (pintype "bidirectional"))
    )
    (net (code "194") (name "Net-(U10-OUT12)") (class "Default")
      (node (ref "RED_17_24") (pin "5") (pinfunction "5_5") (pintype "passive"))
      (node (ref "U10") (pin "17") (pinfunction "OUT12_17") (pintype "bidirectional"))
    )
    (net (code "195") (name "Net-(U10-OUT13)") (class "Default")
      (node (ref "RED_17_24") (pin "6") (pinfunction "6_6") (pintype "passive"))
      (node (ref "U10") (pin "18") (pinfunction "OUT13_18") (pintype "bidirectional"))
    )
    (net (code "196") (name "Net-(U10-OUT14)") (class "Default")
      (node (ref "RED_17_24") (pin "7") (pinfunction "7_7") (pintype "passive"))
      (node (ref "U10") (pin "19") (pinfunction "OUT14_19") (pintype "bidirectional"))
    )
    (net (code "197") (name "Net-(U10-OUT15)") (class "Default")
      (node (ref "RED_17_24") (pin "8") (pinfunction "8_8") (pintype "passive"))
      (node (ref "U10") (pin "20") (pinfunction "OUT15_20") (pintype "bidirectional"))
    )
    (net (code "198") (name "Net-(U10-R-EXT)") (class "Default")
      (node (ref "R10") (pin "2") (pinfunction "2_2") (pintype "passive"))
      (node (ref "U10") (pin "23") (pinfunction "R-EXT_23") (pintype "bidirectional"))
    )
    (net (code "199") (name "Net-(U10-SDI)") (class "Default")
      (node (ref "U10") (pin "2") (pinfunction "SDI_2") (pintype "bidirectional"))
      (node (ref "U9") (pin "22") (pinfunction "SDO_22") (pintype "bidirectional"))
    )
    (net (code "200") (name "Net-(U10-SDO)") (class "Default")
      (node (ref "U10") (pin "22") (pinfunction "SDO_22") (pintype "bidirectional"))
      (node (ref "U11") (pin "2") (pinfunction "SDI_2") (pintype "bidirectional"))
    )
    (net (code "201") (name "Net-(U11-OUT0)") (class "Default")
      (node (ref "RED_25_32") (pin "1") (pinfunction "1_1") (pintype "passive"))
      (node (ref "U11") (pin "5") (pinfunction "OUT0_5") (pintype "bidirectional"))
    )
    (net (code "202") (name "Net-(U11-OUT1)") (class "Default")
      (node (ref "RED_25_32") (pin "2") (pinfunction "2_2") (pintype "passive"))
      (node (ref "U11") (pin "6") (pinfunction "OUT1_6") (pintype "bidirectional"))
    )
    (net (code "203") (name "Net-(U11-OUT2)") (class "Default")
      (node (ref "RED_25_32") (pin "3") (pinfunction "3_3") (pintype "passive"))
      (node (ref "U11") (pin "7") (pinfunction "OUT2_7") (pintype "bidirectional"))
    )
    (net (code "204") (name "Net-(U11-OUT3)") (class "Default")
      (node (ref "RED_25_32") (pin "4") (pinfunction "4_4") (pintype "passive"))
      (node (ref "U11") (pin "8") (pinfunction "OUT3_8") (pintype "bidirectional"))
    )
    (net (code "205") (name "Net-(U11-OUT4)") (class "Default")
      (node (ref "RED_25_32") (pin "5") (pinfunction "5_5") (pintype "passive"))
      (node (ref "U11") (pin "9") (pinfunction "OUT4_9") (pintype "bidirectional"))
    )
    (net (code "206") (name "Net-(U11-OUT5)") (class "Default")
      (node (ref "RED_25_32") (pin "6") (pinfunction "6_6") (pintype "passive"))
      (node (ref "U11") (pin "10") (pinfunction "OUT5_10") (pintype "bidirectional"))
    )
    (net (code "207") (name "Net-(U11-OUT6)") (class "Default")
      (node (ref "RED_25_32") (pin "7") (pinfunction "7_7") (pintype "passive"))
      (node (ref "U11") (pin "11") (pinfunction "OUT6_11") (pintype "bidirectional"))
    )
    (net (code "208") (name "Net-(U11-OUT7)") (class "Default")
      (node (ref "RED_25_32") (pin "8") (pinfunction "8_8") (pintype "passive"))
      (node (ref "U11") (pin "12") (pinfunction "OUT7_12") (pintype "bidirectional"))
    )
    (net (code "209") (name "Net-(U11-OUT8)") (class "Default")
      (node (ref "RED_33_40") (pin "1") (pinfunction "1_1") (pintype "passive"))
      (node (ref "U11") (pin "13") (pinfunction "OUT8_13") (pintype "bidirectional"))
    )
    (net (code "210") (name "Net-(U11-OUT9)") (class "Default")
      (node (ref "RED_33_40") (pin "2") (pinfunction "2_2") (pintype "passive"))
      (node (ref "U11") (pin "14") (pinfunction "OUT9_14") (pintype "bidirectional"))
    )
    (net (code "211") (name "Net-(U11-OUT10)") (class "Default")
      (node (ref "RED_33_40") (pin "3") (pinfunction "3_3") (pintype "passive"))
      (node (ref "U11") (pin "15") (pinfunction "OUT10_15") (pintype "bidirectional"))
    )
    (net (code "212") (name "Net-(U11-OUT11)") (class "Default")
      (node (ref "RED_33_40") (pin "4") (pinfunction "4_4") (pintype "passive"))
      (node (ref "U11") (pin "16") (pinfunction "OUT11_16") (pintype "bidirectional"))
    )
    (net (code "213") (name "Net-(U11-OUT12)") (class "Default")
      (node (ref "RED_33_40") (pin "5") (pinfunction "5_5") (pintype "passive"))
      (node (ref "U11") (pin "17") (pinfunction "OUT12_17") (pintype "bidirectional"))
    )
    (net (code "214") (name "Net-(U11-OUT13)") (class "Default")
      (node (ref "RED_33_40") (pin "6") (pinfunction "6_6") (pintype "passive"))
      (node (ref "U11") (pin "18") (pinfunction "OUT13_18") (pintype "bidirectional"))
    )
    (net (code "215") (name "Net-(U11-OUT14)") (class "Default")
      (node (ref "RED_33_40") (pin "7") (pinfunction "7_7") (pintype "passive"))
      (node (ref "U11") (pin "19") (pinfunction "OUT14_19") (pintype "bidirectional"))
    )
    (net (code "216") (name "Net-(U11-OUT15)") (class "Default")
      (node (ref "RED_33_40") (pin "8") (pinfunction "8_8") (pintype "passive"))
      (node (ref "U11") (pin "20") (pinfunction "OUT15_20") (pintype "bidirectional"))
    )
    (net (code "217") (name "Net-(U11-R-EXT)") (class "Default")
      (node (ref "R11") (pin "2") (pinfunction "2_2") (pintype "passive"))
      (node (ref "U11") (pin "23") (pinfunction "R-EXT_23") (pintype "bidirectional"))
    )
    (net (code "218") (name "Net-(U11-SDO)") (class "Default")
      (node (ref "U11") (pin "22") (pinfunction "SDO_22") (pintype "bidirectional"))
      (node (ref "U12") (pin "2") (pinfunction "SDI_2") (pintype "bidirectional"))
    )
    (net (code "219") (name "Net-(U12-OUT0)") (class "Default")
      (node (ref "RED_41_48") (pin "1") (pinfunction "1_1") (pintype "passive"))
      (node (ref "U12") (pin "5") (pinfunction "OUT0_5") (pintype "bidirectional"))
    )
    (net (code "220") (name "Net-(U12-OUT1)") (class "Default")
      (node (ref "RED_41_48") (pin "2") (pinfunction "2_2") (pintype "passive"))
      (node (ref "U12") (pin "6") (pinfunction "OUT1_6") (pintype "bidirectional"))
    )
    (net (code "221") (name "Net-(U12-OUT2)") (class "Default")
      (node (ref "RED_41_48") (pin "3") (pinfunction "3_3") (pintype "passive"))
      (node (ref "U12") (pin "7") (pinfunction "OUT2_7") (pintype "bidirectional"))
    )
    (net (code "222") (name "Net-(U12-OUT3)") (class "Default")
      (node (ref "RED_41_48") (pin "4") (pinfunction "4_4") (pintype "passive"))
      (node (ref "U12") (pin "8") (pinfunction "OUT3_8") (pintype "bidirectional"))
    )
    (net (code "223") (name "Net-(U12-OUT4)") (class "Default")
      (node (ref "RED_41_48") (pin "5") (pinfunction "5_5") (pintype "passive"))
      (node (ref "U12") (pin "9") (pinfunction "OUT4_9") (pintype "bidirectional"))
    )
    (net (code "224") (name "Net-(U12-OUT5)") (class "Default")
      (node (ref "RED_41_48") (pin "6") (pinfunction "6_6") (pintype "passive"))
      (node (ref "U12") (pin "10") (pinfunction "OUT5_10") (pintype "bidirectional"))
    )
    (net (code "225") (name "Net-(U12-OUT6)") (class "Default")
      (node (ref "RED_41_48") (pin "7") (pinfunction "7_7") (pintype "passive"))
      (node (ref "U12") (pin "11") (pinfunction "OUT6_11") (pintype "bidirectional"))
    )
    (net (code "226") (name "Net-(U12-OUT7)") (class "Default")
      (node (ref "RED_41_48") (pin "8") (pinfunction "8_8") (pintype "passive"))
      (node (ref "U12") (pin "12") (pinfunction "OUT7_12") (pintype "bidirectional"))
    )
    (net (code "227") (name "Net-(U12-OUT8)") (class "Default")
      (node (ref "RED_49_56") (pin "1") (pinfunction "1_1") (pintype "passive"))
      (node (ref "U12") (pin "13") (pinfunction "OUT8_13") (pintype "bidirectional"))
    )
    (net (code "228") (name "Net-(U12-OUT9)") (class "Default")
      (node (ref "RED_49_56") (pin "2") (pinfunction "2_2") (pintype "passive"))
      (node (ref "U12") (pin "14") (pinfunction "OUT9_14") (pintype "bidirectional"))
    )
    (net (code "229") (name "Net-(U12-OUT10)") (class "Default")
      (node (ref "RED_49_56") (pin "3") (pinfunction "3_3") (pintype "passive"))
      (node (ref "U12") (pin "15") (pinfunction "OUT10_15") (pintype "bidirectional"))
    )
    (net (code "230") (name "Net-(U12-OUT11)") (class "Default")
      (node (ref "RED_49_56") (pin "4") (pinfunction "4_4") (pintype "passive"))
      (node (ref "U12") (pin "16") (pinfunction "OUT11_16") (pintype "bidirectional"))
    )
    (net (code "231") (name "Net-(U12-OUT12)") (class "Default")
      (node (ref "RED_49_56") (pin "5") (pinfunction "5_5") (pintype "passive"))
      (node (ref "U12") (pin "17") (pinfunction "OUT12_17") (pintype "bidirectional"))
    )
    (net (code "232") (name "Net-(U12-OUT13)") (class "Default")
      (node (ref "RED_49_56") (pin "6") (pinfunction "6_6") (pintype "passive"))
      (node (ref "U12") (pin "18") (pinfunction "OUT13_18") (pintype "bidirectional"))
    )
    (net (code "233") (name "Net-(U12-OUT14)") (class "Default")
      (node (ref "RED_49_56") (pin "7") (pinfunction "7_7") (pintype "passive"))
      (node (ref "U12") (pin "19") (pinfunction "OUT14_19") (pintype "bidirectional"))
    )
    (net (code "234") (name "Net-(U12-OUT15)") (class "Default")
      (node (ref "RED_49_56") (pin "8") (pinfunction "8_8") (pintype "passive"))
      (node (ref "U12") (pin "20") (pinfunction "OUT15_20") (pintype "bidirectional"))
    )
    (net (code "235") (name "Net-(U12-R-EXT)") (class "Default")
      (node (ref "R12") (pin "2") (pinfunction "2_2") (pintype "passive"))
      (node (ref "U12") (pin "23") (pinfunction "R-EXT_23") (pintype "bidirectional"))
    )
    (net (code "236") (name "Net-(U13-OUT0)") (class "Default")
      (node (ref "RED_57_64") (pin "1") (pinfunction "1_1") (pintype "passive"))
      (node (ref "U13") (pin "5") (pinfunction "OUT0_5") (pintype "bidirectional"))
    )
    (net (code "237") (name "Net-(U13-OUT1)") (class "Default")
      (node (ref "RED_57_64") (pin "2") (pinfunction "2_2") (pintype "passive"))
      (node (ref "U13") (pin "6") (pinfunction "OUT1_6") (pintype "bidirectional"))
    )
    (net (code "238") (name "Net-(U13-OUT2)") (class "Default")
      (node (ref "RED_57_64") (pin "3") (pinfunction "3_3") (pintype "passive"))
      (node (ref "U13") (pin "7") (pinfunction "OUT2_7") (pintype "bidirectional"))
    )
    (net (code "239") (name "Net-(U13-OUT3)") (class "Default")
      (node (ref "RED_57_64") (pin "4") (pinfunction "4_4") (pintype "passive"))
      (node (ref "U13") (pin "8") (pinfunction "OUT3_8") (pintype "bidirectional"))
    )
    (net (code "240") (name "Net-(U13-OUT4)") (class "Default")
      (node (ref "RED_57_64") (pin "5") (pinfunction "5_5") (pintype "passive"))
      (node (ref "U13") (pin "9") (pinfunction "OUT4_9") (pintype "bidirectional"))
    )
    (net (code "241") (name "Net-(U13-OUT5)") (class "Default")
      (node (ref "RED_57_64") (pin "6") (pinfunction "6_6") (pintype "passive"))
      (node (ref "U13") (pin "10") (pinfunction "OUT5_10") (pintype "bidirectional"))
    )
    (net (code "242") (name "Net-(U13-OUT6)") (class "Default")
      (node (ref "RED_57_64") (pin "7") (pinfunction "7_7") (pintype "passive"))
      (node (ref "U13") (pin "11") (pinfunction "OUT6_11") (pintype "bidirectional"))
    )
    (net (code "243") (name "Net-(U13-OUT7)") (class "Default")
      (node (ref "RED_57_64") (pin "8") (pinfunction "8_8") (pintype "passive"))
      (node (ref "U13") (pin "12") (pinfunction "OUT7_12") (pintype "bidirectional"))
    )
    (net (code "244") (name "Net-(U13-R-EXT)") (class "Default")
      (node (ref "R13") (pin "2") (pinfunction "2_2") (pintype "passive"))
      (node (ref "U13") (pin "23") (pinfunction "R-EXT_23") (pintype "bidirectional"))
    )
    (net (code "245") (name "unconnected-(U13-OUT8-Pad13)") (class "Default")
      (node (ref "U13") (pin "13") (pinfunction "OUT8_13") (pintype "bidirectional"))
    )
    (net (code "246") (name "unconnected-(U13-OUT9-Pad14)") (class "Default")
      (node (ref "U13") (pin "14") (pinfunction "OUT9_14") (pintype "bidirectional"))
    )
    (net (code "247") (name "unconnected-(U13-OUT10-Pad15)") (class "Default")
      (node (ref "U13") (pin "15") (pinfunction "OUT10_15") (pintype "bidirectional"))
    )
    (net (code "248") (name "unconnected-(U13-OUT11-Pad16)") (class "Default")
      (node (ref "U13") (pin "16") (pinfunction "OUT11_16") (pintype "bidirectional"))
    )
    (net (code "249") (name "unconnected-(U13-OUT12-Pad17)") (class "Default")
      (node (ref "U13") (pin "17") (pinfunction "OUT12_17") (pintype "bidirectional"))
    )
    (net (code "250") (name "unconnected-(U13-OUT13-Pad18)") (class "Default")
      (node (ref "U13") (pin "18") (pinfunction "OUT13_18") (pintype "bidirectional"))
    )
    (net (code "251") (name "unconnected-(U13-OUT14-Pad19)") (class "Default")
      (node (ref "U13") (pin "19") (pinfunction "OUT14_19") (pintype "bidirectional"))
    )
    (net (code "252") (name "unconnected-(U13-OUT15-Pad20)") (class "Default")
      (node (ref "U13") (pin "20") (pinfunction "OUT15_20") (pintype "bidirectional"))
    )
    (net (code "253") (name "unconnected-(U13-SDO-Pad22)") (class "Default")
      (node (ref "U13") (pin "22") (pinfunction "SDO_22") (pintype "bidirectional"))
    )
    (net (code "254") (name "unconnected-(U14A-A1-Pad2)") (class "Default")
      (node (ref "U14") (pin "2") (pinfunction "A1_2") (pintype "input"))
    )
    (net (code "255") (name "unconnected-(U14A-A2-Pad4)") (class "Default")
      (node (ref "U14") (pin "4") (pinfunction "A2_4") (pintype "input"))
    )
    (net (code "256") (name "unconnected-(U14A-A4-Pad8)") (class "Default")
      (node (ref "U14") (pin "8") (pinfunction "A4_8") (pintype "input"))
    )
    (net (code "257") (name "unconnected-(U14A-Y1-Pad18)") (class "Default")
      (node (ref "U14") (pin "18") (pinfunction "Y1_18") (pintype "tri_state"))
    )
    (net (code "258") (name "unconnected-(U14A-Y2-Pad16)") (class "Default")
      (node (ref "U14") (pin "16") (pinfunction "Y2_16") (pintype "tri_state"))
    )
    (net (code "259") (name "unconnected-(U14A-Y4-Pad12)") (class "Default")
      (node (ref "U14") (pin "12") (pinfunction "Y4_12") (pintype "tri_state"))
    )
  )
)
